# Logic_Engine_-_Rear_SK6812.net
KiCad netlist of a schematic drawn in EAGLE
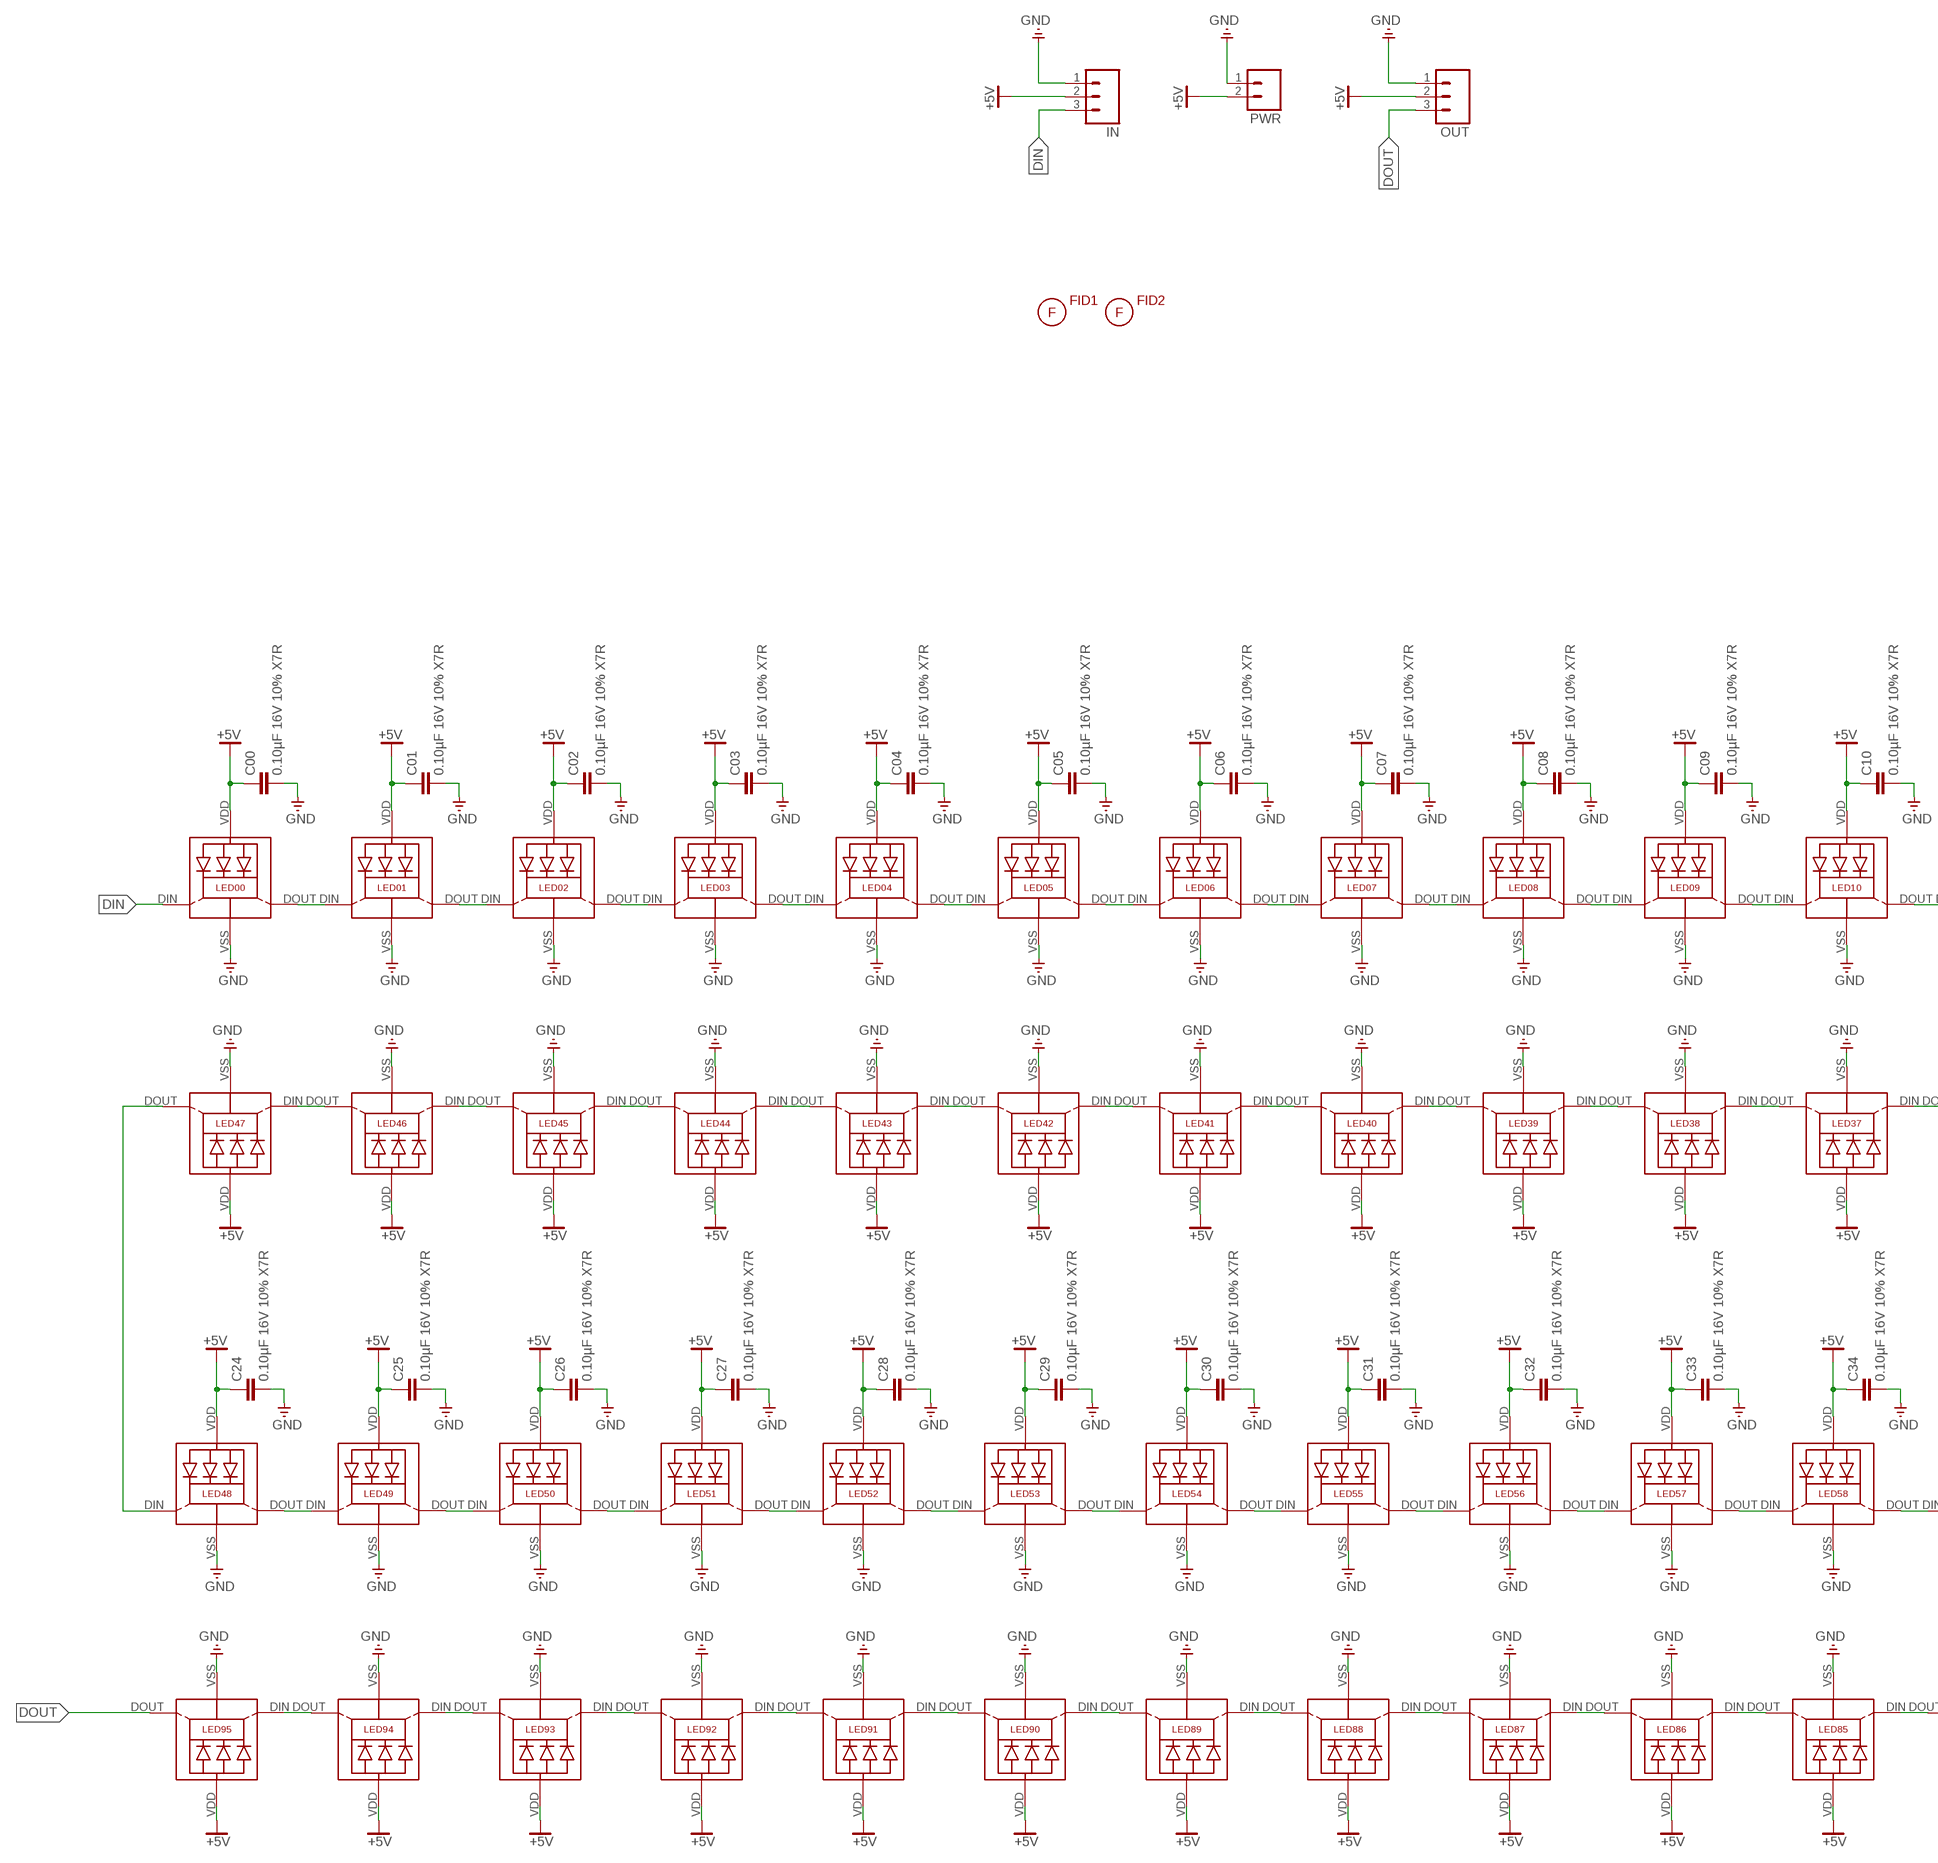
[diagram p0: schematic, sheet 1, part 1 of 2]
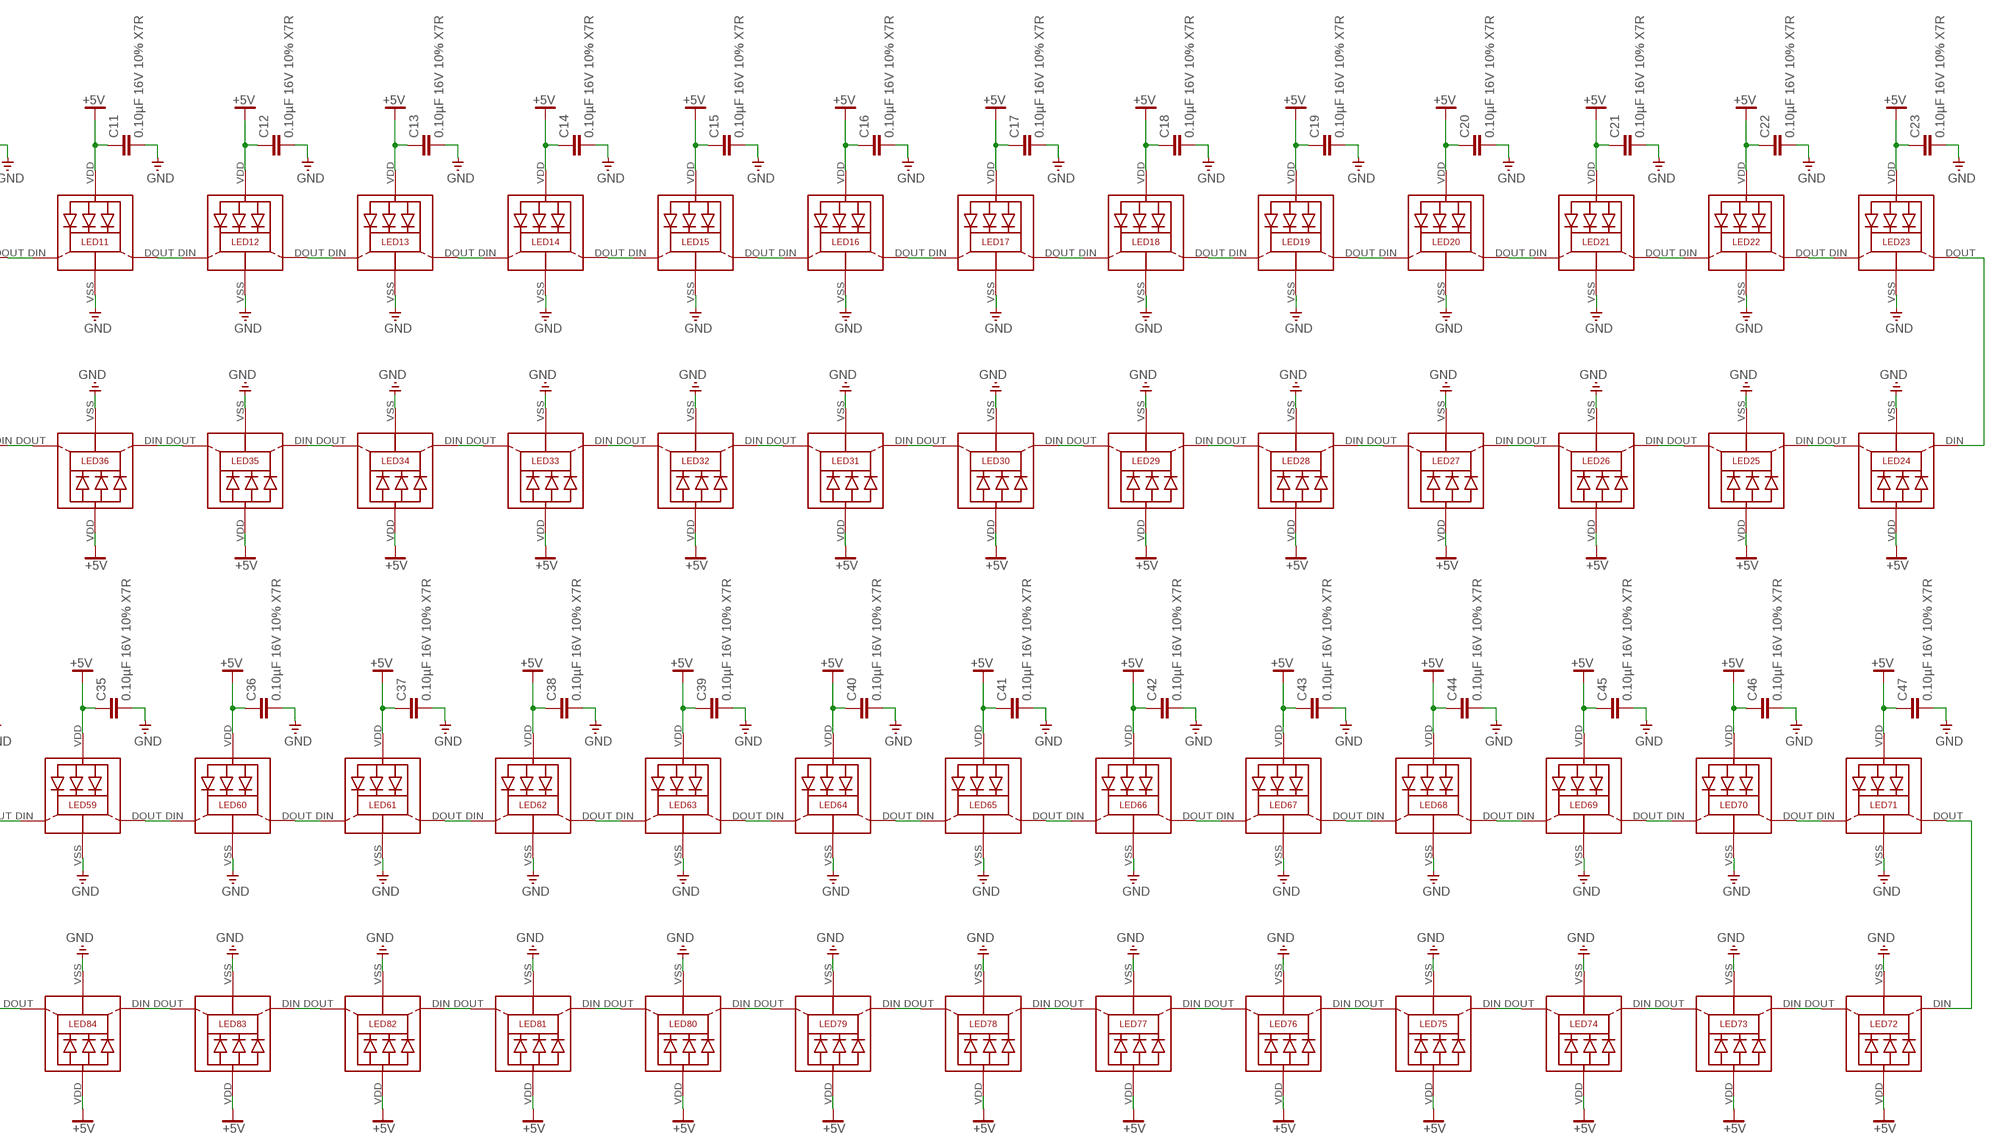
[diagram p1: schematic, sheet 1, part 2 of 2]

(export (version "E")
  (design (tool "Eeschema 10.0.6"))
  (components
    (comp (ref "C00")
      (value "0.10µF 16V 10% X7R")
      (footprint "eagle-import:C0603")
      (libsource (lib "eagle-import") (part "C-EUC0603"))
    )
    (comp (ref "C01")
      (value "0.10µF 16V 10% X7R")
      (footprint "eagle-import:C0603")
      (libsource (lib "eagle-import") (part "C-EUC0603"))
    )
    (comp (ref "C02")
      (value "0.10µF 16V 10% X7R")
      (footprint "eagle-import:C0603")
      (libsource (lib "eagle-import") (part "C-EUC0603"))
    )
    (comp (ref "C03")
      (value "0.10µF 16V 10% X7R")
      (footprint "eagle-import:C0603")
      (libsource (lib "eagle-import") (part "C-EUC0603"))
    )
    (comp (ref "C04")
      (value "0.10µF 16V 10% X7R")
      (footprint "eagle-import:C0603")
      (libsource (lib "eagle-import") (part "C-EUC0603"))
    )
    (comp (ref "C05")
      (value "0.10µF 16V 10% X7R")
      (footprint "eagle-import:C0603")
      (libsource (lib "eagle-import") (part "C-EUC0603"))
    )
    (comp (ref "C06")
      (value "0.10µF 16V 10% X7R")
      (footprint "eagle-import:C0603")
      (libsource (lib "eagle-import") (part "C-EUC0603"))
    )
    (comp (ref "C07")
      (value "0.10µF 16V 10% X7R")
      (footprint "eagle-import:C0603")
      (libsource (lib "eagle-import") (part "C-EUC0603"))
    )
    (comp (ref "C08")
      (value "0.10µF 16V 10% X7R")
      (footprint "eagle-import:C0603")
      (libsource (lib "eagle-import") (part "C-EUC0603"))
    )
    (comp (ref "C09")
      (value "0.10µF 16V 10% X7R")
      (footprint "eagle-import:C0603")
      (libsource (lib "eagle-import") (part "C-EUC0603"))
    )
    (comp (ref "C10")
      (value "0.10µF 16V 10% X7R")
      (footprint "eagle-import:C0603")
      (libsource (lib "eagle-import") (part "C-EUC0603"))
    )
    (comp (ref "C11")
      (value "0.10µF 16V 10% X7R")
      (footprint "eagle-import:C0603")
      (libsource (lib "eagle-import") (part "C-EUC0603"))
    )
    (comp (ref "C12")
      (value "0.10µF 16V 10% X7R")
      (footprint "eagle-import:C0603")
      (libsource (lib "eagle-import") (part "C-EUC0603"))
    )
    (comp (ref "C13")
      (value "0.10µF 16V 10% X7R")
      (footprint "eagle-import:C0603")
      (libsource (lib "eagle-import") (part "C-EUC0603"))
    )
    (comp (ref "C14")
      (value "0.10µF 16V 10% X7R")
      (footprint "eagle-import:C0603")
      (libsource (lib "eagle-import") (part "C-EUC0603"))
    )
    (comp (ref "C15")
      (value "0.10µF 16V 10% X7R")
      (footprint "eagle-import:C0603")
      (libsource (lib "eagle-import") (part "C-EUC0603"))
    )
    (comp (ref "C16")
      (value "0.10µF 16V 10% X7R")
      (footprint "eagle-import:C0603")
      (libsource (lib "eagle-import") (part "C-EUC0603"))
    )
    (comp (ref "C17")
      (value "0.10µF 16V 10% X7R")
      (footprint "eagle-import:C0603")
      (libsource (lib "eagle-import") (part "C-EUC0603"))
    )
    (comp (ref "C18")
      (value "0.10µF 16V 10% X7R")
      (footprint "eagle-import:C0603")
      (libsource (lib "eagle-import") (part "C-EUC0603"))
    )
    (comp (ref "C19")
      (value "0.10µF 16V 10% X7R")
      (footprint "eagle-import:C0603")
      (libsource (lib "eagle-import") (part "C-EUC0603"))
    )
    (comp (ref "C20")
      (value "0.10µF 16V 10% X7R")
      (footprint "eagle-import:C0603")
      (libsource (lib "eagle-import") (part "C-EUC0603"))
    )
    (comp (ref "C21")
      (value "0.10µF 16V 10% X7R")
      (footprint "eagle-import:C0603")
      (libsource (lib "eagle-import") (part "C-EUC0603"))
    )
    (comp (ref "C22")
      (value "0.10µF 16V 10% X7R")
      (footprint "eagle-import:C0603")
      (libsource (lib "eagle-import") (part "C-EUC0603"))
    )
    (comp (ref "C23")
      (value "0.10µF 16V 10% X7R")
      (footprint "eagle-import:C0603")
      (libsource (lib "eagle-import") (part "C-EUC0603"))
    )
    (comp (ref "C24")
      (value "0.10µF 16V 10% X7R")
      (footprint "eagle-import:C0603")
      (libsource (lib "eagle-import") (part "C-EUC0603"))
    )
    (comp (ref "C25")
      (value "0.10µF 16V 10% X7R")
      (footprint "eagle-import:C0603")
      (libsource (lib "eagle-import") (part "C-EUC0603"))
    )
    (comp (ref "C26")
      (value "0.10µF 16V 10% X7R")
      (footprint "eagle-import:C0603")
      (libsource (lib "eagle-import") (part "C-EUC0603"))
    )
    (comp (ref "C27")
      (value "0.10µF 16V 10% X7R")
      (footprint "eagle-import:C0603")
      (libsource (lib "eagle-import") (part "C-EUC0603"))
    )
    (comp (ref "C28")
      (value "0.10µF 16V 10% X7R")
      (footprint "eagle-import:C0603")
      (libsource (lib "eagle-import") (part "C-EUC0603"))
    )
    (comp (ref "C29")
      (value "0.10µF 16V 10% X7R")
      (footprint "eagle-import:C0603")
      (libsource (lib "eagle-import") (part "C-EUC0603"))
    )
    (comp (ref "C30")
      (value "0.10µF 16V 10% X7R")
      (footprint "eagle-import:C0603")
      (libsource (lib "eagle-import") (part "C-EUC0603"))
    )
    (comp (ref "C31")
      (value "0.10µF 16V 10% X7R")
      (footprint "eagle-import:C0603")
      (libsource (lib "eagle-import") (part "C-EUC0603"))
    )
    (comp (ref "C32")
      (value "0.10µF 16V 10% X7R")
      (footprint "eagle-import:C0603")
      (libsource (lib "eagle-import") (part "C-EUC0603"))
    )
    (comp (ref "C33")
      (value "0.10µF 16V 10% X7R")
      (footprint "eagle-import:C0603")
      (libsource (lib "eagle-import") (part "C-EUC0603"))
    )
    (comp (ref "C34")
      (value "0.10µF 16V 10% X7R")
      (footprint "eagle-import:C0603")
      (libsource (lib "eagle-import") (part "C-EUC0603"))
    )
    (comp (ref "C35")
      (value "0.10µF 16V 10% X7R")
      (footprint "eagle-import:C0603")
      (libsource (lib "eagle-import") (part "C-EUC0603"))
    )
    (comp (ref "C36")
      (value "0.10µF 16V 10% X7R")
      (footprint "eagle-import:C0603")
      (libsource (lib "eagle-import") (part "C-EUC0603"))
    )
    (comp (ref "C37")
      (value "0.10µF 16V 10% X7R")
      (footprint "eagle-import:C0603")
      (libsource (lib "eagle-import") (part "C-EUC0603"))
    )
    (comp (ref "C38")
      (value "0.10µF 16V 10% X7R")
      (footprint "eagle-import:C0603")
      (libsource (lib "eagle-import") (part "C-EUC0603"))
    )
    (comp (ref "C39")
      (value "0.10µF 16V 10% X7R")
      (footprint "eagle-import:C0603")
      (libsource (lib "eagle-import") (part "C-EUC0603"))
    )
    (comp (ref "C40")
      (value "0.10µF 16V 10% X7R")
      (footprint "eagle-import:C0603")
      (libsource (lib "eagle-import") (part "C-EUC0603"))
    )
    (comp (ref "C41")
      (value "0.10µF 16V 10% X7R")
      (footprint "eagle-import:C0603")
      (libsource (lib "eagle-import") (part "C-EUC0603"))
    )
    (comp (ref "C42")
      (value "0.10µF 16V 10% X7R")
      (footprint "eagle-import:C0603")
      (libsource (lib "eagle-import") (part "C-EUC0603"))
    )
    (comp (ref "C43")
      (value "0.10µF 16V 10% X7R")
      (footprint "eagle-import:C0603")
      (libsource (lib "eagle-import") (part "C-EUC0603"))
    )
    (comp (ref "C44")
      (value "0.10µF 16V 10% X7R")
      (footprint "eagle-import:C0603")
      (libsource (lib "eagle-import") (part "C-EUC0603"))
    )
    (comp (ref "C45")
      (value "0.10µF 16V 10% X7R")
      (footprint "eagle-import:C0603")
      (libsource (lib "eagle-import") (part "C-EUC0603"))
    )
    (comp (ref "C46")
      (value "0.10µF 16V 10% X7R")
      (footprint "eagle-import:C0603")
      (libsource (lib "eagle-import") (part "C-EUC0603"))
    )
    (comp (ref "C47")
      (value "0.10µF 16V 10% X7R")
      (footprint "eagle-import:C0603")
      (libsource (lib "eagle-import") (part "C-EUC0603"))
    )
    (comp (ref "FID1")
      (value "FIDUCIAL")
      (footprint "eagle-import:FIDUCIAL_G15")
      (libsource (lib "eagle-import") (part "FIDUCIAL"))
    )
    (comp (ref "FID2")
      (value "FIDUCIAL")
      (footprint "eagle-import:FIDUCIAL_G15")
      (libsource (lib "eagle-import") (part "FIDUCIAL"))
    )
    (comp (ref "IN")
      (value "M03PTH")
      (footprint "eagle-import:1X03")
      (libsource (lib "eagle-import") (part "M03PTH"))
    )
    (comp (ref "LED00")
      (value "SK6812MINI")
      (footprint "eagle-import:SK6812MINI")
      (libsource (lib "eagle-import") (part "WS2812BSK6812MINI"))
    )
    (comp (ref "LED01")
      (value "SK6812MINI")
      (footprint "eagle-import:SK6812MINI")
      (libsource (lib "eagle-import") (part "WS2812BSK6812MINI"))
    )
    (comp (ref "LED02")
      (value "SK6812MINI")
      (footprint "eagle-import:SK6812MINI")
      (libsource (lib "eagle-import") (part "WS2812BSK6812MINI"))
    )
    (comp (ref "LED03")
      (value "SK6812MINI")
      (footprint "eagle-import:SK6812MINI")
      (libsource (lib "eagle-import") (part "WS2812BSK6812MINI"))
    )
    (comp (ref "LED04")
      (value "SK6812MINI")
      (footprint "eagle-import:SK6812MINI")
      (libsource (lib "eagle-import") (part "WS2812BSK6812MINI"))
    )
    (comp (ref "LED05")
      (value "SK6812MINI")
      (footprint "eagle-import:SK6812MINI")
      (libsource (lib "eagle-import") (part "WS2812BSK6812MINI"))
    )
    (comp (ref "LED06")
      (value "SK6812MINI")
      (footprint "eagle-import:SK6812MINI")
      (libsource (lib "eagle-import") (part "WS2812BSK6812MINI"))
    )
    (comp (ref "LED07")
      (value "SK6812MINI")
      (footprint "eagle-import:SK6812MINI")
      (libsource (lib "eagle-import") (part "WS2812BSK6812MINI"))
    )
    (comp (ref "LED08")
      (value "SK6812MINI")
      (footprint "eagle-import:SK6812MINI")
      (libsource (lib "eagle-import") (part "WS2812BSK6812MINI"))
    )
    (comp (ref "LED09")
      (value "SK6812MINI")
      (footprint "eagle-import:SK6812MINI")
      (libsource (lib "eagle-import") (part "WS2812BSK6812MINI"))
    )
    (comp (ref "LED10")
      (value "SK6812MINI")
      (footprint "eagle-import:SK6812MINI")
      (libsource (lib "eagle-import") (part "WS2812BSK6812MINI"))
    )
    (comp (ref "LED11")
      (value "SK6812MINI")
      (footprint "eagle-import:SK6812MINI")
      (libsource (lib "eagle-import") (part "WS2812BSK6812MINI"))
    )
    (comp (ref "LED12")
      (value "SK6812MINI")
      (footprint "eagle-import:SK6812MINI")
      (libsource (lib "eagle-import") (part "WS2812BSK6812MINI"))
    )
    (comp (ref "LED13")
      (value "SK6812MINI")
      (footprint "eagle-import:SK6812MINI")
      (libsource (lib "eagle-import") (part "WS2812BSK6812MINI"))
    )
    (comp (ref "LED14")
      (value "SK6812MINI")
      (footprint "eagle-import:SK6812MINI")
      (libsource (lib "eagle-import") (part "WS2812BSK6812MINI"))
    )
    (comp (ref "LED15")
      (value "SK6812MINI")
      (footprint "eagle-import:SK6812MINI")
      (libsource (lib "eagle-import") (part "WS2812BSK6812MINI"))
    )
    (comp (ref "LED16")
      (value "SK6812MINI")
      (footprint "eagle-import:SK6812MINI")
      (libsource (lib "eagle-import") (part "WS2812BSK6812MINI"))
    )
    (comp (ref "LED17")
      (value "SK6812MINI")
      (footprint "eagle-import:SK6812MINI")
      (libsource (lib "eagle-import") (part "WS2812BSK6812MINI"))
    )
    (comp (ref "LED18")
      (value "SK6812MINI")
      (footprint "eagle-import:SK6812MINI")
      (libsource (lib "eagle-import") (part "WS2812BSK6812MINI"))
    )
    (comp (ref "LED19")
      (value "SK6812MINI")
      (footprint "eagle-import:SK6812MINI")
      (libsource (lib "eagle-import") (part "WS2812BSK6812MINI"))
    )
    (comp (ref "LED20")
      (value "SK6812MINI")
      (footprint "eagle-import:SK6812MINI")
      (libsource (lib "eagle-import") (part "WS2812BSK6812MINI"))
    )
    (comp (ref "LED21")
      (value "SK6812MINI")
      (footprint "eagle-import:SK6812MINI")
      (libsource (lib "eagle-import") (part "WS2812BSK6812MINI"))
    )
    (comp (ref "LED22")
      (value "SK6812MINI")
      (footprint "eagle-import:SK6812MINI")
      (libsource (lib "eagle-import") (part "WS2812BSK6812MINI"))
    )
    (comp (ref "LED23")
      (value "SK6812MINI")
      (footprint "eagle-import:SK6812MINI")
      (libsource (lib "eagle-import") (part "WS2812BSK6812MINI"))
    )
    (comp (ref "LED24")
      (value "SK6812MINI")
      (footprint "eagle-import:SK6812MINI")
      (libsource (lib "eagle-import") (part "WS2812BSK6812MINI"))
    )
    (comp (ref "LED25")
      (value "SK6812MINI")
      (footprint "eagle-import:SK6812MINI")
      (libsource (lib "eagle-import") (part "WS2812BSK6812MINI"))
    )
    (comp (ref "LED26")
      (value "SK6812MINI")
      (footprint "eagle-import:SK6812MINI")
      (libsource (lib "eagle-import") (part "WS2812BSK6812MINI"))
    )
    (comp (ref "LED27")
      (value "SK6812MINI")
      (footprint "eagle-import:SK6812MINI")
      (libsource (lib "eagle-import") (part "WS2812BSK6812MINI"))
    )
    (comp (ref "LED28")
      (value "SK6812MINI")
      (footprint "eagle-import:SK6812MINI")
      (libsource (lib "eagle-import") (part "WS2812BSK6812MINI"))
    )
    (comp (ref "LED29")
      (value "SK6812MINI")
      (footprint "eagle-import:SK6812MINI")
      (libsource (lib "eagle-import") (part "WS2812BSK6812MINI"))
    )
    (comp (ref "LED30")
      (value "SK6812MINI")
      (footprint "eagle-import:SK6812MINI")
      (libsource (lib "eagle-import") (part "WS2812BSK6812MINI"))
    )
    (comp (ref "LED31")
      (value "SK6812MINI")
      (footprint "eagle-import:SK6812MINI")
      (libsource (lib "eagle-import") (part "WS2812BSK6812MINI"))
    )
    (comp (ref "LED32")
      (value "SK6812MINI")
      (footprint "eagle-import:SK6812MINI")
      (libsource (lib "eagle-import") (part "WS2812BSK6812MINI"))
    )
    (comp (ref "LED33")
      (value "SK6812MINI")
      (footprint "eagle-import:SK6812MINI")
      (libsource (lib "eagle-import") (part "WS2812BSK6812MINI"))
    )
    (comp (ref "LED34")
      (value "SK6812MINI")
      (footprint "eagle-import:SK6812MINI")
      (libsource (lib "eagle-import") (part "WS2812BSK6812MINI"))
    )
    (comp (ref "LED35")
      (value "SK6812MINI")
      (footprint "eagle-import:SK6812MINI")
      (libsource (lib "eagle-import") (part "WS2812BSK6812MINI"))
    )
    (comp (ref "LED36")
      (value "SK6812MINI")
      (footprint "eagle-import:SK6812MINI")
      (libsource (lib "eagle-import") (part "WS2812BSK6812MINI"))
    )
    (comp (ref "LED37")
      (value "SK6812MINI")
      (footprint "eagle-import:SK6812MINI")
      (libsource (lib "eagle-import") (part "WS2812BSK6812MINI"))
    )
    (comp (ref "LED38")
      (value "SK6812MINI")
      (footprint "eagle-import:SK6812MINI")
      (libsource (lib "eagle-import") (part "WS2812BSK6812MINI"))
    )
    (comp (ref "LED39")
      (value "SK6812MINI")
      (footprint "eagle-import:SK6812MINI")
      (libsource (lib "eagle-import") (part "WS2812BSK6812MINI"))
    )
    (comp (ref "LED40")
      (value "SK6812MINI")
      (footprint "eagle-import:SK6812MINI")
      (libsource (lib "eagle-import") (part "WS2812BSK6812MINI"))
    )
    (comp (ref "LED41")
      (value "SK6812MINI")
      (footprint "eagle-import:SK6812MINI")
      (libsource (lib "eagle-import") (part "WS2812BSK6812MINI"))
    )
    (comp (ref "LED42")
      (value "SK6812MINI")
      (footprint "eagle-import:SK6812MINI")
      (libsource (lib "eagle-import") (part "WS2812BSK6812MINI"))
    )
    (comp (ref "LED43")
      (value "SK6812MINI")
      (footprint "eagle-import:SK6812MINI")
      (libsource (lib "eagle-import") (part "WS2812BSK6812MINI"))
    )
    (comp (ref "LED44")
      (value "SK6812MINI")
      (footprint "eagle-import:SK6812MINI")
      (libsource (lib "eagle-import") (part "WS2812BSK6812MINI"))
    )
    (comp (ref "LED45")
      (value "SK6812MINI")
      (footprint "eagle-import:SK6812MINI")
      (libsource (lib "eagle-import") (part "WS2812BSK6812MINI"))
    )
    (comp (ref "LED46")
      (value "SK6812MINI")
      (footprint "eagle-import:SK6812MINI")
      (libsource (lib "eagle-import") (part "WS2812BSK6812MINI"))
    )
    (comp (ref "LED47")
      (value "SK6812MINI")
      (footprint "eagle-import:SK6812MINI")
      (libsource (lib "eagle-import") (part "WS2812BSK6812MINI"))
    )
    (comp (ref "LED48")
      (value "SK6812MINI")
      (footprint "eagle-import:SK6812MINI")
      (libsource (lib "eagle-import") (part "WS2812BSK6812MINI"))
    )
    (comp (ref "LED49")
      (value "SK6812MINI")
      (footprint "eagle-import:SK6812MINI")
      (libsource (lib "eagle-import") (part "WS2812BSK6812MINI"))
    )
    (comp (ref "LED50")
      (value "SK6812MINI")
      (footprint "eagle-import:SK6812MINI")
      (libsource (lib "eagle-import") (part "WS2812BSK6812MINI"))
    )
    (comp (ref "LED51")
      (value "SK6812MINI")
      (footprint "eagle-import:SK6812MINI")
      (libsource (lib "eagle-import") (part "WS2812BSK6812MINI"))
    )
    (comp (ref "LED52")
      (value "SK6812MINI")
      (footprint "eagle-import:SK6812MINI")
      (libsource (lib "eagle-import") (part "WS2812BSK6812MINI"))
    )
    (comp (ref "LED53")
      (value "SK6812MINI")
      (footprint "eagle-import:SK6812MINI")
      (libsource (lib "eagle-import") (part "WS2812BSK6812MINI"))
    )
    (comp (ref "LED54")
      (value "SK6812MINI")
      (footprint "eagle-import:SK6812MINI")
      (libsource (lib "eagle-import") (part "WS2812BSK6812MINI"))
    )
    (comp (ref "LED55")
      (value "SK6812MINI")
      (footprint "eagle-import:SK6812MINI")
      (libsource (lib "eagle-import") (part "WS2812BSK6812MINI"))
    )
    (comp (ref "LED56")
      (value "SK6812MINI")
      (footprint "eagle-import:SK6812MINI")
      (libsource (lib "eagle-import") (part "WS2812BSK6812MINI"))
    )
    (comp (ref "LED57")
      (value "SK6812MINI")
      (footprint "eagle-import:SK6812MINI")
      (libsource (lib "eagle-import") (part "WS2812BSK6812MINI"))
    )
    (comp (ref "LED58")
      (value "SK6812MINI")
      (footprint "eagle-import:SK6812MINI")
      (libsource (lib "eagle-import") (part "WS2812BSK6812MINI"))
    )
    (comp (ref "LED59")
      (value "SK6812MINI")
      (footprint "eagle-import:SK6812MINI")
      (libsource (lib "eagle-import") (part "WS2812BSK6812MINI"))
    )
    (comp (ref "LED60")
      (value "SK6812MINI")
      (footprint "eagle-import:SK6812MINI")
      (libsource (lib "eagle-import") (part "WS2812BSK6812MINI"))
    )
    (comp (ref "LED61")
      (value "SK6812MINI")
      (footprint "eagle-import:SK6812MINI")
      (libsource (lib "eagle-import") (part "WS2812BSK6812MINI"))
    )
    (comp (ref "LED62")
      (value "SK6812MINI")
      (footprint "eagle-import:SK6812MINI")
      (libsource (lib "eagle-import") (part "WS2812BSK6812MINI"))
    )
    (comp (ref "LED63")
      (value "SK6812MINI")
      (footprint "eagle-import:SK6812MINI")
      (libsource (lib "eagle-import") (part "WS2812BSK6812MINI"))
    )
    (comp (ref "LED64")
      (value "SK6812MINI")
      (footprint "eagle-import:SK6812MINI")
      (libsource (lib "eagle-import") (part "WS2812BSK6812MINI"))
    )
    (comp (ref "LED65")
      (value "SK6812MINI")
      (footprint "eagle-import:SK6812MINI")
      (libsource (lib "eagle-import") (part "WS2812BSK6812MINI"))
    )
    (comp (ref "LED66")
      (value "SK6812MINI")
      (footprint "eagle-import:SK6812MINI")
      (libsource (lib "eagle-import") (part "WS2812BSK6812MINI"))
    )
    (comp (ref "LED67")
      (value "SK6812MINI")
      (footprint "eagle-import:SK6812MINI")
      (libsource (lib "eagle-import") (part "WS2812BSK6812MINI"))
    )
    (comp (ref "LED68")
      (value "SK6812MINI")
      (footprint "eagle-import:SK6812MINI")
      (libsource (lib "eagle-import") (part "WS2812BSK6812MINI"))
    )
    (comp (ref "LED69")
      (value "SK6812MINI")
      (footprint "eagle-import:SK6812MINI")
      (libsource (lib "eagle-import") (part "WS2812BSK6812MINI"))
    )
    (comp (ref "LED70")
      (value "SK6812MINI")
      (footprint "eagle-import:SK6812MINI")
      (libsource (lib "eagle-import") (part "WS2812BSK6812MINI"))
    )
    (comp (ref "LED71")
      (value "SK6812MINI")
      (footprint "eagle-import:SK6812MINI")
      (libsource (lib "eagle-import") (part "WS2812BSK6812MINI"))
    )
    (comp (ref "LED72")
      (value "SK6812MINI")
      (footprint "eagle-import:SK6812MINI")
      (libsource (lib "eagle-import") (part "WS2812BSK6812MINI"))
    )
    (comp (ref "LED73")
      (value "SK6812MINI")
      (footprint "eagle-import:SK6812MINI")
      (libsource (lib "eagle-import") (part "WS2812BSK6812MINI"))
    )
    (comp (ref "LED74")
      (value "SK6812MINI")
      (footprint "eagle-import:SK6812MINI")
      (libsource (lib "eagle-import") (part "WS2812BSK6812MINI"))
    )
    (comp (ref "LED75")
      (value "SK6812MINI")
      (footprint "eagle-import:SK6812MINI")
      (libsource (lib "eagle-import") (part "WS2812BSK6812MINI"))
    )
    (comp (ref "LED76")
      (value "SK6812MINI")
      (footprint "eagle-import:SK6812MINI")
      (libsource (lib "eagle-import") (part "WS2812BSK6812MINI"))
    )
    (comp (ref "LED77")
      (value "SK6812MINI")
      (footprint "eagle-import:SK6812MINI")
      (libsource (lib "eagle-import") (part "WS2812BSK6812MINI"))
    )
    (comp (ref "LED78")
      (value "SK6812MINI")
      (footprint "eagle-import:SK6812MINI")
      (libsource (lib "eagle-import") (part "WS2812BSK6812MINI"))
    )
    (comp (ref "LED79")
      (value "SK6812MINI")
      (footprint "eagle-import:SK6812MINI")
      (libsource (lib "eagle-import") (part "WS2812BSK6812MINI"))
    )
    (comp (ref "LED80")
      (value "SK6812MINI")
      (footprint "eagle-import:SK6812MINI")
      (libsource (lib "eagle-import") (part "WS2812BSK6812MINI"))
    )
    (comp (ref "LED81")
      (value "SK6812MINI")
      (footprint "eagle-import:SK6812MINI")
      (libsource (lib "eagle-import") (part "WS2812BSK6812MINI"))
    )
    (comp (ref "LED82")
      (value "SK6812MINI")
      (footprint "eagle-import:SK6812MINI")
      (libsource (lib "eagle-import") (part "WS2812BSK6812MINI"))
    )
    (comp (ref "LED83")
      (value "SK6812MINI")
      (footprint "eagle-import:SK6812MINI")
      (libsource (lib "eagle-import") (part "WS2812BSK6812MINI"))
    )
    (comp (ref "LED84")
      (value "SK6812MINI")
      (footprint "eagle-import:SK6812MINI")
      (libsource (lib "eagle-import") (part "WS2812BSK6812MINI"))
    )
    (comp (ref "LED85")
      (value "SK6812MINI")
      (footprint "eagle-import:SK6812MINI")
      (libsource (lib "eagle-import") (part "WS2812BSK6812MINI"))
    )
    (comp (ref "LED86")
      (value "SK6812MINI")
      (footprint "eagle-import:SK6812MINI")
      (libsource (lib "eagle-import") (part "WS2812BSK6812MINI"))
    )
    (comp (ref "LED87")
      (value "SK6812MINI")
      (footprint "eagle-import:SK6812MINI")
      (libsource (lib "eagle-import") (part "WS2812BSK6812MINI"))
    )
    (comp (ref "LED88")
      (value "SK6812MINI")
      (footprint "eagle-import:SK6812MINI")
      (libsource (lib "eagle-import") (part "WS2812BSK6812MINI"))
    )
    (comp (ref "LED89")
      (value "SK6812MINI")
      (footprint "eagle-import:SK6812MINI")
      (libsource (lib "eagle-import") (part "WS2812BSK6812MINI"))
    )
    (comp (ref "LED90")
      (value "SK6812MINI")
      (footprint "eagle-import:SK6812MINI")
      (libsource (lib "eagle-import") (part "WS2812BSK6812MINI"))
    )
    (comp (ref "LED91")
      (value "SK6812MINI")
      (footprint "eagle-import:SK6812MINI")
      (libsource (lib "eagle-import") (part "WS2812BSK6812MINI"))
    )
    (comp (ref "LED92")
      (value "SK6812MINI")
      (footprint "eagle-import:SK6812MINI")
      (libsource (lib "eagle-import") (part "WS2812BSK6812MINI"))
    )
    (comp (ref "LED93")
      (value "SK6812MINI")
      (footprint "eagle-import:SK6812MINI")
      (libsource (lib "eagle-import") (part "WS2812BSK6812MINI"))
    )
    (comp (ref "LED94")
      (value "SK6812MINI")
      (footprint "eagle-import:SK6812MINI")
      (libsource (lib "eagle-import") (part "WS2812BSK6812MINI"))
    )
    (comp (ref "LED95")
      (value "SK6812MINI")
      (footprint "eagle-import:SK6812MINI")
      (libsource (lib "eagle-import") (part "WS2812BSK6812MINI"))
    )
    (comp (ref "OUT")
      (value "M03PTH")
      (footprint "eagle-import:1X03")
      (libsource (lib "eagle-import") (part "M03PTH"))
    )
    (comp (ref "PWR")
      (value "M02PTH")
      (footprint "eagle-import:1X02")
      (libsource (lib "eagle-import") (part "M02PTH"))
    )
  )
  (nets
    (net (code "1") (name "+5V") (class "Default")
      (node (ref "C00") (pin "1") (pinfunction "1_1") (pintype "passive"))
      (node (ref "C01") (pin "1") (pinfunction "1_1") (pintype "passive"))
      (node (ref "C02") (pin "1") (pinfunction "1_1") (pintype "passive"))
      (node (ref "C03") (pin "1") (pinfunction "1_1") (pintype "passive"))
      (node (ref "C04") (pin "1") (pinfunction "1_1") (pintype "passive"))
      (node (ref "C05") (pin "1") (pinfunction "1_1") (pintype "passive"))
      (node (ref "C06") (pin "1") (pinfunction "1_1") (pintype "passive"))
      (node (ref "C07") (pin "1") (pinfunction "1_1") (pintype "passive"))
      (node (ref "C08") (pin "1") (pinfunction "1_1") (pintype "passive"))
      (node (ref "C09") (pin "1") (pinfunction "1_1") (pintype "passive"))
      (node (ref "C10") (pin "1") (pinfunction "1_1") (pintype "passive"))
      (node (ref "C11") (pin "1") (pinfunction "1_1") (pintype "passive"))
      (node (ref "C12") (pin "1") (pinfunction "1_1") (pintype "passive"))
      (node (ref "C13") (pin "1") (pinfunction "1_1") (pintype "passive"))
      (node (ref "C14") (pin "1") (pinfunction "1_1") (pintype "passive"))
      (node (ref "C15") (pin "1") (pinfunction "1_1") (pintype "passive"))
      (node (ref "C16") (pin "1") (pinfunction "1_1") (pintype "passive"))
      (node (ref "C17") (pin "1") (pinfunction "1_1") (pintype "passive"))
      (node (ref "C18") (pin "1") (pinfunction "1_1") (pintype "passive"))
      (node (ref "C19") (pin "1") (pinfunction "1_1") (pintype "passive"))
      (node (ref "C20") (pin "1") (pinfunction "1_1") (pintype "passive"))
      (node (ref "C21") (pin "1") (pinfunction "1_1") (pintype "passive"))
      (node (ref "C22") (pin "1") (pinfunction "1_1") (pintype "passive"))
      (node (ref "C23") (pin "1") (pinfunction "1_1") (pintype "passive"))
      (node (ref "C24") (pin "1") (pinfunction "1_1") (pintype "passive"))
      (node (ref "C25") (pin "1") (pinfunction "1_1") (pintype "passive"))
      (node (ref "C26") (pin "1") (pinfunction "1_1") (pintype "passive"))
      (node (ref "C27") (pin "1") (pinfunction "1_1") (pintype "passive"))
      (node (ref "C28") (pin "1") (pinfunction "1_1") (pintype "passive"))
      (node (ref "C29") (pin "1") (pinfunction "1_1") (pintype "passive"))
      (node (ref "C30") (pin "1") (pinfunction "1_1") (pintype "passive"))
      (node (ref "C31") (pin "1") (pinfunction "1_1") (pintype "passive"))
      (node (ref "C32") (pin "1") (pinfunction "1_1") (pintype "passive"))
      (node (ref "C33") (pin "1") (pinfunction "1_1") (pintype "passive"))
      (node (ref "C34") (pin "1") (pinfunction "1_1") (pintype "passive"))
      (node (ref "C35") (pin "1") (pinfunction "1_1") (pintype "passive"))
      (node (ref "C36") (pin "1") (pinfunction "1_1") (pintype "passive"))
      (node (ref "C37") (pin "1") (pinfunction "1_1") (pintype "passive"))
      (node (ref "C38") (pin "1") (pinfunction "1_1") (pintype "passive"))
      (node (ref "C39") (pin "1") (pinfunction "1_1") (pintype "passive"))
      (node (ref "C40") (pin "1") (pinfunction "1_1") (pintype "passive"))
      (node (ref "C41") (pin "1") (pinfunction "1_1") (pintype "passive"))
      (node (ref "C42") (pin "1") (pinfunction "1_1") (pintype "passive"))
      (node (ref "C43") (pin "1") (pinfunction "1_1") (pintype "passive"))
      (node (ref "C44") (pin "1") (pinfunction "1_1") (pintype "passive"))
      (node (ref "C45") (pin "1") (pinfunction "1_1") (pintype "passive"))
      (node (ref "C46") (pin "1") (pinfunction "1_1") (pintype "passive"))
      (node (ref "C47") (pin "1") (pinfunction "1_1") (pintype "passive"))
      (node (ref "IN") (pin "2") (pinfunction "2_2") (pintype "passive"))
      (node (ref "LED00") (pin "VDD") (pinfunction "VDD_VDD") (pintype "power_in"))
      (node (ref "LED01") (pin "VDD") (pinfunction "VDD_VDD") (pintype "power_in"))
      (node (ref "LED02") (pin "VDD") (pinfunction "VDD_VDD") (pintype "power_in"))
      (node (ref "LED03") (pin "VDD") (pinfunction "VDD_VDD") (pintype "power_in"))
      (node (ref "LED04") (pin "VDD") (pinfunction "VDD_VDD") (pintype "power_in"))
      (node (ref "LED05") (pin "VDD") (pinfunction "VDD_VDD") (pintype "power_in"))
      (node (ref "LED06") (pin "VDD") (pinfunction "VDD_VDD") (pintype "power_in"))
      (node (ref "LED07") (pin "VDD") (pinfunction "VDD_VDD") (pintype "power_in"))
      (node (ref "LED08") (pin "VDD") (pinfunction "VDD_VDD") (pintype "power_in"))
      (node (ref "LED09") (pin "VDD") (pinfunction "VDD_VDD") (pintype "power_in"))
      (node (ref "LED10") (pin "VDD") (pinfunction "VDD_VDD") (pintype "power_in"))
      (node (ref "LED11") (pin "VDD") (pinfunction "VDD_VDD") (pintype "power_in"))
      (node (ref "LED12") (pin "VDD") (pinfunction "VDD_VDD") (pintype "power_in"))
      (node (ref "LED13") (pin "VDD") (pinfunction "VDD_VDD") (pintype "power_in"))
      (node (ref "LED14") (pin "VDD") (pinfunction "VDD_VDD") (pintype "power_in"))
      (node (ref "LED15") (pin "VDD") (pinfunction "VDD_VDD") (pintype "power_in"))
      (node (ref "LED16") (pin "VDD") (pinfunction "VDD_VDD") (pintype "power_in"))
      (node (ref "LED17") (pin "VDD") (pinfunction "VDD_VDD") (pintype "power_in"))
      (node (ref "LED18") (pin "VDD") (pinfunction "VDD_VDD") (pintype "power_in"))
      (node (ref "LED19") (pin "VDD") (pinfunction "VDD_VDD") (pintype "power_in"))
      (node (ref "LED20") (pin "VDD") (pinfunction "VDD_VDD") (pintype "power_in"))
      (node (ref "LED21") (pin "VDD") (pinfunction "VDD_VDD") (pintype "power_in"))
      (node (ref "LED22") (pin "VDD") (pinfunction "VDD_VDD") (pintype "power_in"))
      (node (ref "LED23") (pin "VDD") (pinfunction "VDD_VDD") (pintype "power_in"))
      (node (ref "LED24") (pin "VDD") (pinfunction "VDD_VDD") (pintype "power_in"))
      (node (ref "LED25") (pin "VDD") (pinfunction "VDD_VDD") (pintype "power_in"))
      (node (ref "LED26") (pin "VDD") (pinfunction "VDD_VDD") (pintype "power_in"))
      (node (ref "LED27") (pin "VDD") (pinfunction "VDD_VDD") (pintype "power_in"))
      (node (ref "LED28") (pin "VDD") (pinfunction "VDD_VDD") (pintype "power_in"))
      (node (ref "LED29") (pin "VDD") (pinfunction "VDD_VDD") (pintype "power_in"))
      (node (ref "LED30") (pin "VDD") (pinfunction "VDD_VDD") (pintype "power_in"))
      (node (ref "LED31") (pin "VDD") (pinfunction "VDD_VDD") (pintype "power_in"))
      (node (ref "LED32") (pin "VDD") (pinfunction "VDD_VDD") (pintype "power_in"))
      (node (ref "LED33") (pin "VDD") (pinfunction "VDD_VDD") (pintype "power_in"))
      (node (ref "LED34") (pin "VDD") (pinfunction "VDD_VDD") (pintype "power_in"))
      (node (ref "LED35") (pin "VDD") (pinfunction "VDD_VDD") (pintype "power_in"))
      (node (ref "LED36") (pin "VDD") (pinfunction "VDD_VDD") (pintype "power_in"))
      (node (ref "LED37") (pin "VDD") (pinfunction "VDD_VDD") (pintype "power_in"))
      (node (ref "LED38") (pin "VDD") (pinfunction "VDD_VDD") (pintype "power_in"))
      (node (ref "LED39") (pin "VDD") (pinfunction "VDD_VDD") (pintype "power_in"))
      (node (ref "LED40") (pin "VDD") (pinfunction "VDD_VDD") (pintype "power_in"))
      (node (ref "LED41") (pin "VDD") (pinfunction "VDD_VDD") (pintype "power_in"))
      (node (ref "LED42") (pin "VDD") (pinfunction "VDD_VDD") (pintype "power_in"))
      (node (ref "LED43") (pin "VDD") (pinfunction "VDD_VDD") (pintype "power_in"))
      (node (ref "LED44") (pin "VDD") (pinfunction "VDD_VDD") (pintype "power_in"))
      (node (ref "LED45") (pin "VDD") (pinfunction "VDD_VDD") (pintype "power_in"))
      (node (ref "LED46") (pin "VDD") (pinfunction "VDD_VDD") (pintype "power_in"))
      (node (ref "LED47") (pin "VDD") (pinfunction "VDD_VDD") (pintype "power_in"))
      (node (ref "LED48") (pin "VDD") (pinfunction "VDD_VDD") (pintype "power_in"))
      (node (ref "LED49") (pin "VDD") (pinfunction "VDD_VDD") (pintype "power_in"))
      (node (ref "LED50") (pin "VDD") (pinfunction "VDD_VDD") (pintype "power_in"))
      (node (ref "LED51") (pin "VDD") (pinfunction "VDD_VDD") (pintype "power_in"))
      (node (ref "LED52") (pin "VDD") (pinfunction "VDD_VDD") (pintype "power_in"))
      (node (ref "LED53") (pin "VDD") (pinfunction "VDD_VDD") (pintype "power_in"))
      (node (ref "LED54") (pin "VDD") (pinfunction "VDD_VDD") (pintype "power_in"))
      (node (ref "LED55") (pin "VDD") (pinfunction "VDD_VDD") (pintype "power_in"))
      (node (ref "LED56") (pin "VDD") (pinfunction "VDD_VDD") (pintype "power_in"))
      (node (ref "LED57") (pin "VDD") (pinfunction "VDD_VDD") (pintype "power_in"))
      (node (ref "LED58") (pin "VDD") (pinfunction "VDD_VDD") (pintype "power_in"))
      (node (ref "LED59") (pin "VDD") (pinfunction "VDD_VDD") (pintype "power_in"))
      (node (ref "LED60") (pin "VDD") (pinfunction "VDD_VDD") (pintype "power_in"))
      (node (ref "LED61") (pin "VDD") (pinfunction "VDD_VDD") (pintype "power_in"))
      (node (ref "LED62") (pin "VDD") (pinfunction "VDD_VDD") (pintype "power_in"))
      (node (ref "LED63") (pin "VDD") (pinfunction "VDD_VDD") (pintype "power_in"))
      (node (ref "LED64") (pin "VDD") (pinfunction "VDD_VDD") (pintype "power_in"))
      (node (ref "LED65") (pin "VDD") (pinfunction "VDD_VDD") (pintype "power_in"))
      (node (ref "LED66") (pin "VDD") (pinfunction "VDD_VDD") (pintype "power_in"))
      (node (ref "LED67") (pin "VDD") (pinfunction "VDD_VDD") (pintype "power_in"))
      (node (ref "LED68") (pin "VDD") (pinfunction "VDD_VDD") (pintype "power_in"))
      (node (ref "LED69") (pin "VDD") (pinfunction "VDD_VDD") (pintype "power_in"))
      (node (ref "LED70") (pin "VDD") (pinfunction "VDD_VDD") (pintype "power_in"))
      (node (ref "LED71") (pin "VDD") (pinfunction "VDD_VDD") (pintype "power_in"))
      (node (ref "LED72") (pin "VDD") (pinfunction "VDD_VDD") (pintype "power_in"))
      (node (ref "LED73") (pin "VDD") (pinfunction "VDD_VDD") (pintype "power_in"))
      (node (ref "LED74") (pin "VDD") (pinfunction "VDD_VDD") (pintype "power_in"))
      (node (ref "LED75") (pin "VDD") (pinfunction "VDD_VDD") (pintype "power_in"))
      (node (ref "LED76") (pin "VDD") (pinfunction "VDD_VDD") (pintype "power_in"))
      (node (ref "LED77") (pin "VDD") (pinfunction "VDD_VDD") (pintype "power_in"))
      (node (ref "LED78") (pin "VDD") (pinfunction "VDD_VDD") (pintype "power_in"))
      (node (ref "LED79") (pin "VDD") (pinfunction "VDD_VDD") (pintype "power_in"))
      (node (ref "LED80") (pin "VDD") (pinfunction "VDD_VDD") (pintype "power_in"))
      (node (ref "LED81") (pin "VDD") (pinfunction "VDD_VDD") (pintype "power_in"))
      (node (ref "LED82") (pin "VDD") (pinfunction "VDD_VDD") (pintype "power_in"))
      (node (ref "LED83") (pin "VDD") (pinfunction "VDD_VDD") (pintype "power_in"))
      (node (ref "LED84") (pin "VDD") (pinfunction "VDD_VDD") (pintype "power_in"))
      (node (ref "LED85") (pin "VDD") (pinfunction "VDD_VDD") (pintype "power_in"))
      (node (ref "LED86") (pin "VDD") (pinfunction "VDD_VDD") (pintype "power_in"))
      (node (ref "LED87") (pin "VDD") (pinfunction "VDD_VDD") (pintype "power_in"))
      (node (ref "LED88") (pin "VDD") (pinfunction "VDD_VDD") (pintype "power_in"))
      (node (ref "LED89") (pin "VDD") (pinfunction "VDD_VDD") (pintype "power_in"))
      (node (ref "LED90") (pin "VDD") (pinfunction "VDD_VDD") (pintype "power_in"))
      (node (ref "LED91") (pin "VDD") (pinfunction "VDD_VDD") (pintype "power_in"))
      (node (ref "LED92") (pin "VDD") (pinfunction "VDD_VDD") (pintype "power_in"))
      (node (ref "LED93") (pin "VDD") (pinfunction "VDD_VDD") (pintype "power_in"))
      (node (ref "LED94") (pin "VDD") (pinfunction "VDD_VDD") (pintype "power_in"))
      (node (ref "LED95") (pin "VDD") (pinfunction "VDD_VDD") (pintype "power_in"))
      (node (ref "OUT") (pin "2") (pinfunction "2_2") (pintype "passive"))
      (node (ref "PWR") (pin "2") (pinfunction "2_2") (pintype "passive"))
    )
    (net (code "2") (name "DIN") (class "Default")
      (node (ref "IN") (pin "3") (pinfunction "3_3") (pintype "passive"))
      (node (ref "LED00") (pin "DIN") (pinfunction "DI_DIN") (pintype "input"))
    )
    (net (code "3") (name "DOUT") (class "Default")
      (node (ref "LED95") (pin "DOUT") (pinfunction "DO_DOUT") (pintype "output"))
      (node (ref "OUT") (pin "3") (pinfunction "3_3") (pintype "passive"))
    )
    (net (code "4") (name "GND") (class "Default")
      (node (ref "C00") (pin "2") (pinfunction "2_2") (pintype "passive"))
      (node (ref "C01") (pin "2") (pinfunction "2_2") (pintype "passive"))
      (node (ref "C02") (pin "2") (pinfunction "2_2") (pintype "passive"))
      (node (ref "C03") (pin "2") (pinfunction "2_2") (pintype "passive"))
      (node (ref "C04") (pin "2") (pinfunction "2_2") (pintype "passive"))
      (node (ref "C05") (pin "2") (pinfunction "2_2") (pintype "passive"))
      (node (ref "C06") (pin "2") (pinfunction "2_2") (pintype "passive"))
      (node (ref "C07") (pin "2") (pinfunction "2_2") (pintype "passive"))
      (node (ref "C08") (pin "2") (pinfunction "2_2") (pintype "passive"))
      (node (ref "C09") (pin "2") (pinfunction "2_2") (pintype "passive"))
      (node (ref "C10") (pin "2") (pinfunction "2_2") (pintype "passive"))
      (node (ref "C11") (pin "2") (pinfunction "2_2") (pintype "passive"))
      (node (ref "C12") (pin "2") (pinfunction "2_2") (pintype "passive"))
      (node (ref "C13") (pin "2") (pinfunction "2_2") (pintype "passive"))
      (node (ref "C14") (pin "2") (pinfunction "2_2") (pintype "passive"))
      (node (ref "C15") (pin "2") (pinfunction "2_2") (pintype "passive"))
      (node (ref "C16") (pin "2") (pinfunction "2_2") (pintype "passive"))
      (node (ref "C17") (pin "2") (pinfunction "2_2") (pintype "passive"))
      (node (ref "C18") (pin "2") (pinfunction "2_2") (pintype "passive"))
      (node (ref "C19") (pin "2") (pinfunction "2_2") (pintype "passive"))
      (node (ref "C20") (pin "2") (pinfunction "2_2") (pintype "passive"))
      (node (ref "C21") (pin "2") (pinfunction "2_2") (pintype "passive"))
      (node (ref "C22") (pin "2") (pinfunction "2_2") (pintype "passive"))
      (node (ref "C23") (pin "2") (pinfunction "2_2") (pintype "passive"))
      (node (ref "C24") (pin "2") (pinfunction "2_2") (pintype "passive"))
      (node (ref "C25") (pin "2") (pinfunction "2_2") (pintype "passive"))
      (node (ref "C26") (pin "2") (pinfunction "2_2") (pintype "passive"))
      (node (ref "C27") (pin "2") (pinfunction "2_2") (pintype "passive"))
      (node (ref "C28") (pin "2") (pinfunction "2_2") (pintype "passive"))
      (node (ref "C29") (pin "2") (pinfunction "2_2") (pintype "passive"))
      (node (ref "C30") (pin "2") (pinfunction "2_2") (pintype "passive"))
      (node (ref "C31") (pin "2") (pinfunction "2_2") (pintype "passive"))
      (node (ref "C32") (pin "2") (pinfunction "2_2") (pintype "passive"))
      (node (ref "C33") (pin "2") (pinfunction "2_2") (pintype "passive"))
      (node (ref "C34") (pin "2") (pinfunction "2_2") (pintype "passive"))
      (node (ref "C35") (pin "2") (pinfunction "2_2") (pintype "passive"))
      (node (ref "C36") (pin "2") (pinfunction "2_2") (pintype "passive"))
      (node (ref "C37") (pin "2") (pinfunction "2_2") (pintype "passive"))
      (node (ref "C38") (pin "2") (pinfunction "2_2") (pintype "passive"))
      (node (ref "C39") (pin "2") (pinfunction "2_2") (pintype "passive"))
      (node (ref "C40") (pin "2") (pinfunction "2_2") (pintype "passive"))
      (node (ref "C41") (pin "2") (pinfunction "2_2") (pintype "passive"))
      (node (ref "C42") (pin "2") (pinfunction "2_2") (pintype "passive"))
      (node (ref "C43") (pin "2") (pinfunction "2_2") (pintype "passive"))
      (node (ref "C44") (pin "2") (pinfunction "2_2") (pintype "passive"))
      (node (ref "C45") (pin "2") (pinfunction "2_2") (pintype "passive"))
      (node (ref "C46") (pin "2") (pinfunction "2_2") (pintype "passive"))
      (node (ref "C47") (pin "2") (pinfunction "2_2") (pintype "passive"))
      (node (ref "IN") (pin "1") (pinfunction "1_1") (pintype "passive"))
      (node (ref "LED00") (pin "VSS") (pinfunction "GND_VSS") (pintype "power_in"))
      (node (ref "LED01") (pin "VSS") (pinfunction "GND_VSS") (pintype "power_in"))
      (node (ref "LED02") (pin "VSS") (pinfunction "GND_VSS") (pintype "power_in"))
      (node (ref "LED03") (pin "VSS") (pinfunction "GND_VSS") (pintype "power_in"))
      (node (ref "LED04") (pin "VSS") (pinfunction "GND_VSS") (pintype "power_in"))
      (node (ref "LED05") (pin "VSS") (pinfunction "GND_VSS") (pintype "power_in"))
      (node (ref "LED06") (pin "VSS") (pinfunction "GND_VSS") (pintype "power_in"))
      (node (ref "LED07") (pin "VSS") (pinfunction "GND_VSS") (pintype "power_in"))
      (node (ref "LED08") (pin "VSS") (pinfunction "GND_VSS") (pintype "power_in"))
      (node (ref "LED09") (pin "VSS") (pinfunction "GND_VSS") (pintype "power_in"))
      (node (ref "LED10") (pin "VSS") (pinfunction "GND_VSS") (pintype "power_in"))
      (node (ref "LED11") (pin "VSS") (pinfunction "GND_VSS") (pintype "power_in"))
      (node (ref "LED12") (pin "VSS") (pinfunction "GND_VSS") (pintype "power_in"))
      (node (ref "LED13") (pin "VSS") (pinfunction "GND_VSS") (pintype "power_in"))
      (node (ref "LED14") (pin "VSS") (pinfunction "GND_VSS") (pintype "power_in"))
      (node (ref "LED15") (pin "VSS") (pinfunction "GND_VSS") (pintype "power_in"))
      (node (ref "LED16") (pin "VSS") (pinfunction "GND_VSS") (pintype "power_in"))
      (node (ref "LED17") (pin "VSS") (pinfunction "GND_VSS") (pintype "power_in"))
      (node (ref "LED18") (pin "VSS") (pinfunction "GND_VSS") (pintype "power_in"))
      (node (ref "LED19") (pin "VSS") (pinfunction "GND_VSS") (pintype "power_in"))
      (node (ref "LED20") (pin "VSS") (pinfunction "GND_VSS") (pintype "power_in"))
      (node (ref "LED21") (pin "VSS") (pinfunction "GND_VSS") (pintype "power_in"))
      (node (ref "LED22") (pin "VSS") (pinfunction "GND_VSS") (pintype "power_in"))
      (node (ref "LED23") (pin "VSS") (pinfunction "GND_VSS") (pintype "power_in"))
      (node (ref "LED24") (pin "VSS") (pinfunction "GND_VSS") (pintype "power_in"))
      (node (ref "LED25") (pin "VSS") (pinfunction "GND_VSS") (pintype "power_in"))
      (node (ref "LED26") (pin "VSS") (pinfunction "GND_VSS") (pintype "power_in"))
      (node (ref "LED27") (pin "VSS") (pinfunction "GND_VSS") (pintype "power_in"))
      (node (ref "LED28") (pin "VSS") (pinfunction "GND_VSS") (pintype "power_in"))
      (node (ref "LED29") (pin "VSS") (pinfunction "GND_VSS") (pintype "power_in"))
      (node (ref "LED30") (pin "VSS") (pinfunction "GND_VSS") (pintype "power_in"))
      (node (ref "LED31") (pin "VSS") (pinfunction "GND_VSS") (pintype "power_in"))
      (node (ref "LED32") (pin "VSS") (pinfunction "GND_VSS") (pintype "power_in"))
      (node (ref "LED33") (pin "VSS") (pinfunction "GND_VSS") (pintype "power_in"))
      (node (ref "LED34") (pin "VSS") (pinfunction "GND_VSS") (pintype "power_in"))
      (node (ref "LED35") (pin "VSS") (pinfunction "GND_VSS") (pintype "power_in"))
      (node (ref "LED36") (pin "VSS") (pinfunction "GND_VSS") (pintype "power_in"))
      (node (ref "LED37") (pin "VSS") (pinfunction "GND_VSS") (pintype "power_in"))
      (node (ref "LED38") (pin "VSS") (pinfunction "GND_VSS") (pintype "power_in"))
      (node (ref "LED39") (pin "VSS") (pinfunction "GND_VSS") (pintype "power_in"))
      (node (ref "LED40") (pin "VSS") (pinfunction "GND_VSS") (pintype "power_in"))
      (node (ref "LED41") (pin "VSS") (pinfunction "GND_VSS") (pintype "power_in"))
      (node (ref "LED42") (pin "VSS") (pinfunction "GND_VSS") (pintype "power_in"))
      (node (ref "LED43") (pin "VSS") (pinfunction "GND_VSS") (pintype "power_in"))
      (node (ref "LED44") (pin "VSS") (pinfunction "GND_VSS") (pintype "power_in"))
      (node (ref "LED45") (pin "VSS") (pinfunction "GND_VSS") (pintype "power_in"))
      (node (ref "LED46") (pin "VSS") (pinfunction "GND_VSS") (pintype "power_in"))
      (node (ref "LED47") (pin "VSS") (pinfunction "GND_VSS") (pintype "power_in"))
      (node (ref "LED48") (pin "VSS") (pinfunction "GND_VSS") (pintype "power_in"))
      (node (ref "LED49") (pin "VSS") (pinfunction "GND_VSS") (pintype "power_in"))
      (node (ref "LED50") (pin "VSS") (pinfunction "GND_VSS") (pintype "power_in"))
      (node (ref "LED51") (pin "VSS") (pinfunction "GND_VSS") (pintype "power_in"))
      (node (ref "LED52") (pin "VSS") (pinfunction "GND_VSS") (pintype "power_in"))
      (node (ref "LED53") (pin "VSS") (pinfunction "GND_VSS") (pintype "power_in"))
      (node (ref "LED54") (pin "VSS") (pinfunction "GND_VSS") (pintype "power_in"))
      (node (ref "LED55") (pin "VSS") (pinfunction "GND_VSS") (pintype "power_in"))
      (node (ref "LED56") (pin "VSS") (pinfunction "GND_VSS") (pintype "power_in"))
      (node (ref "LED57") (pin "VSS") (pinfunction "GND_VSS") (pintype "power_in"))
      (node (ref "LED58") (pin "VSS") (pinfunction "GND_VSS") (pintype "power_in"))
      (node (ref "LED59") (pin "VSS") (pinfunction "GND_VSS") (pintype "power_in"))
      (node (ref "LED60") (pin "VSS") (pinfunction "GND_VSS") (pintype "power_in"))
      (node (ref "LED61") (pin "VSS") (pinfunction "GND_VSS") (pintype "power_in"))
      (node (ref "LED62") (pin "VSS") (pinfunction "GND_VSS") (pintype "power_in"))
      (node (ref "LED63") (pin "VSS") (pinfunction "GND_VSS") (pintype "power_in"))
      (node (ref "LED64") (pin "VSS") (pinfunction "GND_VSS") (pintype "power_in"))
      (node (ref "LED65") (pin "VSS") (pinfunction "GND_VSS") (pintype "power_in"))
      (node (ref "LED66") (pin "VSS") (pinfunction "GND_VSS") (pintype "power_in"))
      (node (ref "LED67") (pin "VSS") (pinfunction "GND_VSS") (pintype "power_in"))
      (node (ref "LED68") (pin "VSS") (pinfunction "GND_VSS") (pintype "power_in"))
      (node (ref "LED69") (pin "VSS") (pinfunction "GND_VSS") (pintype "power_in"))
      (node (ref "LED70") (pin "VSS") (pinfunction "GND_VSS") (pintype "power_in"))
      (node (ref "LED71") (pin "VSS") (pinfunction "GND_VSS") (pintype "power_in"))
      (node (ref "LED72") (pin "VSS") (pinfunction "GND_VSS") (pintype "power_in"))
      (node (ref "LED73") (pin "VSS") (pinfunction "GND_VSS") (pintype "power_in"))
      (node (ref "LED74") (pin "VSS") (pinfunction "GND_VSS") (pintype "power_in"))
      (node (ref "LED75") (pin "VSS") (pinfunction "GND_VSS") (pintype "power_in"))
      (node (ref "LED76") (pin "VSS") (pinfunction "GND_VSS") (pintype "power_in"))
      (node (ref "LED77") (pin "VSS") (pinfunction "GND_VSS") (pintype "power_in"))
      (node (ref "LED78") (pin "VSS") (pinfunction "GND_VSS") (pintype "power_in"))
      (node (ref "LED79") (pin "VSS") (pinfunction "GND_VSS") (pintype "power_in"))
      (node (ref "LED80") (pin "VSS") (pinfunction "GND_VSS") (pintype "power_in"))
      (node (ref "LED81") (pin "VSS") (pinfunction "GND_VSS") (pintype "power_in"))
      (node (ref "LED82") (pin "VSS") (pinfunction "GND_VSS") (pintype "power_in"))
      (node (ref "LED83") (pin "VSS") (pinfunction "GND_VSS") (pintype "power_in"))
      (node (ref "LED84") (pin "VSS") (pinfunction "GND_VSS") (pintype "power_in"))
      (node (ref "LED85") (pin "VSS") (pinfunction "GND_VSS") (pintype "power_in"))
      (node (ref "LED86") (pin "VSS") (pinfunction "GND_VSS") (pintype "power_in"))
      (node (ref "LED87") (pin "VSS") (pinfunction "GND_VSS") (pintype "power_in"))
      (node (ref "LED88") (pin "VSS") (pinfunction "GND_VSS") (pintype "power_in"))
      (node (ref "LED89") (pin "VSS") (pinfunction "GND_VSS") (pintype "power_in"))
      (node (ref "LED90") (pin "VSS") (pinfunction "GND_VSS") (pintype "power_in"))
      (node (ref "LED91") (pin "VSS") (pinfunction "GND_VSS") (pintype "power_in"))
      (node (ref "LED92") (pin "VSS") (pinfunction "GND_VSS") (pintype "power_in"))
      (node (ref "LED93") (pin "VSS") (pinfunction "GND_VSS") (pintype "power_in"))
      (node (ref "LED94") (pin "VSS") (pinfunction "GND_VSS") (pintype "power_in"))
      (node (ref "LED95") (pin "VSS") (pinfunction "GND_VSS") (pintype "power_in"))
      (node (ref "OUT") (pin "1") (pinfunction "1_1") (pintype "passive"))
      (node (ref "PWR") (pin "1") (pinfunction "1_1") (pintype "passive"))
    )
    (net (code "5") (name "Net-(LED00-DO)") (class "Default")
      (node (ref "LED00") (pin "DOUT") (pinfunction "DO_DOUT") (pintype "output"))
      (node (ref "LED01") (pin "DIN") (pinfunction "DI_DIN") (pintype "input"))
    )
    (net (code "6") (name "Net-(LED01-DO)") (class "Default")
      (node (ref "LED01") (pin "DOUT") (pinfunction "DO_DOUT") (pintype "output"))
      (node (ref "LED02") (pin "DIN") (pinfunction "DI_DIN") (pintype "input"))
    )
    (net (code "7") (name "Net-(LED02-DO)") (class "Default")
      (node (ref "LED02") (pin "DOUT") (pinfunction "DO_DOUT") (pintype "output"))
      (node (ref "LED03") (pin "DIN") (pinfunction "DI_DIN") (pintype "input"))
    )
    (net (code "8") (name "Net-(LED03-DO)") (class "Default")
      (node (ref "LED03") (pin "DOUT") (pinfunction "DO_DOUT") (pintype "output"))
      (node (ref "LED04") (pin "DIN") (pinfunction "DI_DIN") (pintype "input"))
    )
    (net (code "9") (name "Net-(LED04-DO)") (class "Default")
      (node (ref "LED04") (pin "DOUT") (pinfunction "DO_DOUT") (pintype "output"))
      (node (ref "LED05") (pin "DIN") (pinfunction "DI_DIN") (pintype "input"))
    )
    (net (code "10") (name "Net-(LED05-DO)") (class "Default")
      (node (ref "LED05") (pin "DOUT") (pinfunction "DO_DOUT") (pintype "output"))
      (node (ref "LED06") (pin "DIN") (pinfunction "DI_DIN") (pintype "input"))
    )
    (net (code "11") (name "Net-(LED06-DO)") (class "Default")
      (node (ref "LED06") (pin "DOUT") (pinfunction "DO_DOUT") (pintype "output"))
      (node (ref "LED07") (pin "DIN") (pinfunction "DI_DIN") (pintype "input"))
    )
    (net (code "12") (name "Net-(LED07-DO)") (class "Default")
      (node (ref "LED07") (pin "DOUT") (pinfunction "DO_DOUT") (pintype "output"))
      (node (ref "LED08") (pin "DIN") (pinfunction "DI_DIN") (pintype "input"))
    )
    (net (code "13") (name "Net-(LED08-DO)") (class "Default")
      (node (ref "LED08") (pin "DOUT") (pinfunction "DO_DOUT") (pintype "output"))
      (node (ref "LED09") (pin "DIN") (pinfunction "DI_DIN") (pintype "input"))
    )
    (net (code "14") (name "Net-(LED09-DO)") (class "Default")
      (node (ref "LED09") (pin "DOUT") (pinfunction "DO_DOUT") (pintype "output"))
      (node (ref "LED10") (pin "DIN") (pinfunction "DI_DIN") (pintype "input"))
    )
    (net (code "15") (name "Net-(LED10-DO)") (class "Default")
      (node (ref "LED10") (pin "DOUT") (pinfunction "DO_DOUT") (pintype "output"))
      (node (ref "LED11") (pin "DIN") (pinfunction "DI_DIN") (pintype "input"))
    )
    (net (code "16") (name "Net-(LED11-DO)") (class "Default")
      (node (ref "LED11") (pin "DOUT") (pinfunction "DO_DOUT") (pintype "output"))
      (node (ref "LED12") (pin "DIN") (pinfunction "DI_DIN") (pintype "input"))
    )
    (net (code "17") (name "Net-(LED12-DO)") (class "Default")
      (node (ref "LED12") (pin "DOUT") (pinfunction "DO_DOUT") (pintype "output"))
      (node (ref "LED13") (pin "DIN") (pinfunction "DI_DIN") (pintype "input"))
    )
    (net (code "18") (name "Net-(LED13-DO)") (class "Default")
      (node (ref "LED13") (pin "DOUT") (pinfunction "DO_DOUT") (pintype "output"))
      (node (ref "LED14") (pin "DIN") (pinfunction "DI_DIN") (pintype "input"))
    )
    (net (code "19") (name "Net-(LED14-DO)") (class "Default")
      (node (ref "LED14") (pin "DOUT") (pinfunction "DO_DOUT") (pintype "output"))
      (node (ref "LED15") (pin "DIN") (pinfunction "DI_DIN") (pintype "input"))
    )
    (net (code "20") (name "Net-(LED15-DO)") (class "Default")
      (node (ref "LED15") (pin "DOUT") (pinfunction "DO_DOUT") (pintype "output"))
      (node (ref "LED16") (pin "DIN") (pinfunction "DI_DIN") (pintype "input"))
    )
    (net (code "21") (name "Net-(LED16-DO)") (class "Default")
      (node (ref "LED16") (pin "DOUT") (pinfunction "DO_DOUT") (pintype "output"))
      (node (ref "LED17") (pin "DIN") (pinfunction "DI_DIN") (pintype "input"))
    )
    (net (code "22") (name "Net-(LED17-DO)") (class "Default")
      (node (ref "LED17") (pin "DOUT") (pinfunction "DO_DOUT") (pintype "output"))
      (node (ref "LED18") (pin "DIN") (pinfunction "DI_DIN") (pintype "input"))
    )
    (net (code "23") (name "Net-(LED18-DO)") (class "Default")
      (node (ref "LED18") (pin "DOUT") (pinfunction "DO_DOUT") (pintype "output"))
      (node (ref "LED19") (pin "DIN") (pinfunction "DI_DIN") (pintype "input"))
    )
    (net (code "24") (name "Net-(LED19-DO)") (class "Default")
      (node (ref "LED19") (pin "DOUT") (pinfunction "DO_DOUT") (pintype "output"))
      (node (ref "LED20") (pin "DIN") (pinfunction "DI_DIN") (pintype "input"))
    )
    (net (code "25") (name "Net-(LED20-DO)") (class "Default")
      (node (ref "LED20") (pin "DOUT") (pinfunction "DO_DOUT") (pintype "output"))
      (node (ref "LED21") (pin "DIN") (pinfunction "DI_DIN") (pintype "input"))
    )
    (net (code "26") (name "Net-(LED21-DO)") (class "Default")
      (node (ref "LED21") (pin "DOUT") (pinfunction "DO_DOUT") (pintype "output"))
      (node (ref "LED22") (pin "DIN") (pinfunction "DI_DIN") (pintype "input"))
    )
    (net (code "27") (name "Net-(LED22-DO)") (class "Default")
      (node (ref "LED22") (pin "DOUT") (pinfunction "DO_DOUT") (pintype "output"))
      (node (ref "LED23") (pin "DIN") (pinfunction "DI_DIN") (pintype "input"))
    )
    (net (code "28") (name "Net-(LED23-DO)") (class "Default")
      (node (ref "LED23") (pin "DOUT") (pinfunction "DO_DOUT") (pintype "output"))
      (node (ref "LED24") (pin "DIN") (pinfunction "DI_DIN") (pintype "input"))
    )
    (net (code "29") (name "Net-(LED24-DO)") (class "Default")
      (node (ref "LED24") (pin "DOUT") (pinfunction "DO_DOUT") (pintype "output"))
      (node (ref "LED25") (pin "DIN") (pinfunction "DI_DIN") (pintype "input"))
    )
    (net (code "30") (name "Net-(LED25-DO)") (class "Default")
      (node (ref "LED25") (pin "DOUT") (pinfunction "DO_DOUT") (pintype "output"))
      (node (ref "LED26") (pin "DIN") (pinfunction "DI_DIN") (pintype "input"))
    )
    (net (code "31") (name "Net-(LED26-DO)") (class "Default")
      (node (ref "LED26") (pin "DOUT") (pinfunction "DO_DOUT") (pintype "output"))
      (node (ref "LED27") (pin "DIN") (pinfunction "DI_DIN") (pintype "input"))
    )
    (net (code "32") (name "Net-(LED27-DO)") (class "Default")
      (node (ref "LED27") (pin "DOUT") (pinfunction "DO_DOUT") (pintype "output"))
      (node (ref "LED28") (pin "DIN") (pinfunction "DI_DIN") (pintype "input"))
    )
    (net (code "33") (name "Net-(LED28-DO)") (class "Default")
      (node (ref "LED28") (pin "DOUT") (pinfunction "DO_DOUT") (pintype "output"))
      (node (ref "LED29") (pin "DIN") (pinfunction "DI_DIN") (pintype "input"))
    )
    (net (code "34") (name "Net-(LED29-DO)") (class "Default")
      (node (ref "LED29") (pin "DOUT") (pinfunction "DO_DOUT") (pintype "output"))
      (node (ref "LED30") (pin "DIN") (pinfunction "DI_DIN") (pintype "input"))
    )
    (net (code "35") (name "Net-(LED30-DO)") (class "Default")
      (node (ref "LED30") (pin "DOUT") (pinfunction "DO_DOUT") (pintype "output"))
      (node (ref "LED31") (pin "DIN") (pinfunction "DI_DIN") (pintype "input"))
    )
    (net (code "36") (name "Net-(LED31-DO)") (class "Default")
      (node (ref "LED31") (pin "DOUT") (pinfunction "DO_DOUT") (pintype "output"))
      (node (ref "LED32") (pin "DIN") (pinfunction "DI_DIN") (pintype "input"))
    )
    (net (code "37") (name "Net-(LED32-DO)") (class "Default")
      (node (ref "LED32") (pin "DOUT") (pinfunction "DO_DOUT") (pintype "output"))
      (node (ref "LED33") (pin "DIN") (pinfunction "DI_DIN") (pintype "input"))
    )
    (net (code "38") (name "Net-(LED33-DO)") (class "Default")
      (node (ref "LED33") (pin "DOUT") (pinfunction "DO_DOUT") (pintype "output"))
      (node (ref "LED34") (pin "DIN") (pinfunction "DI_DIN") (pintype "input"))
    )
    (net (code "39") (name "Net-(LED34-DO)") (class "Default")
      (node (ref "LED34") (pin "DOUT") (pinfunction "DO_DOUT") (pintype "output"))
      (node (ref "LED35") (pin "DIN") (pinfunction "DI_DIN") (pintype "input"))
    )
    (net (code "40") (name "Net-(LED35-DO)") (class "Default")
      (node (ref "LED35") (pin "DOUT") (pinfunction "DO_DOUT") (pintype "output"))
      (node (ref "LED36") (pin "DIN") (pinfunction "DI_DIN") (pintype "input"))
    )
    (net (code "41") (name "Net-(LED36-DO)") (class "Default")
      (node (ref "LED36") (pin "DOUT") (pinfunction "DO_DOUT") (pintype "output"))
      (node (ref "LED37") (pin "DIN") (pinfunction "DI_DIN") (pintype "input"))
    )
    (net (code "42") (name "Net-(LED37-DO)") (class "Default")
      (node (ref "LED37") (pin "DOUT") (pinfunction "DO_DOUT") (pintype "output"))
      (node (ref "LED38") (pin "DIN") (pinfunction "DI_DIN") (pintype "input"))
    )
    (net (code "43") (name "Net-(LED38-DO)") (class "Default")
      (node (ref "LED38") (pin "DOUT") (pinfunction "DO_DOUT") (pintype "output"))
      (node (ref "LED39") (pin "DIN") (pinfunction "DI_DIN") (pintype "input"))
    )
    (net (code "44") (name "Net-(LED39-DO)") (class "Default")
      (node (ref "LED39") (pin "DOUT") (pinfunction "DO_DOUT") (pintype "output"))
      (node (ref "LED40") (pin "DIN") (pinfunction "DI_DIN") (pintype "input"))
    )
    (net (code "45") (name "Net-(LED40-DO)") (class "Default")
      (node (ref "LED40") (pin "DOUT") (pinfunction "DO_DOUT") (pintype "output"))
      (node (ref "LED41") (pin "DIN") (pinfunction "DI_DIN") (pintype "input"))
    )
    (net (code "46") (name "Net-(LED41-DO)") (class "Default")
      (node (ref "LED41") (pin "DOUT") (pinfunction "DO_DOUT") (pintype "output"))
      (node (ref "LED42") (pin "DIN") (pinfunction "DI_DIN") (pintype "input"))
    )
    (net (code "47") (name "Net-(LED42-DO)") (class "Default")
      (node (ref "LED42") (pin "DOUT") (pinfunction "DO_DOUT") (pintype "output"))
      (node (ref "LED43") (pin "DIN") (pinfunction "DI_DIN") (pintype "input"))
    )
    (net (code "48") (name "Net-(LED43-DO)") (class "Default")
      (node (ref "LED43") (pin "DOUT") (pinfunction "DO_DOUT") (pintype "output"))
      (node (ref "LED44") (pin "DIN") (pinfunction "DI_DIN") (pintype "input"))
    )
    (net (code "49") (name "Net-(LED44-DO)") (class "Default")
      (node (ref "LED44") (pin "DOUT") (pinfunction "DO_DOUT") (pintype "output"))
      (node (ref "LED45") (pin "DIN") (pinfunction "DI_DIN") (pintype "input"))
    )
    (net (code "50") (name "Net-(LED45-DO)") (class "Default")
      (node (ref "LED45") (pin "DOUT") (pinfunction "DO_DOUT") (pintype "output"))
      (node (ref "LED46") (pin "DIN") (pinfunction "DI_DIN") (pintype "input"))
    )
    (net (code "51") (name "Net-(LED46-DO)") (class "Default")
      (node (ref "LED46") (pin "DOUT") (pinfunction "DO_DOUT") (pintype "output"))
      (node (ref "LED47") (pin "DIN") (pinfunction "DI_DIN") (pintype "input"))
    )
    (net (code "52") (name "Net-(LED47-DO)") (class "Default")
      (node (ref "LED47") (pin "DOUT") (pinfunction "DO_DOUT") (pintype "output"))
      (node (ref "LED48") (pin "DIN") (pinfunction "DI_DIN") (pintype "input"))
    )
    (net (code "53") (name "Net-(LED48-DO)") (class "Default")
      (node (ref "LED48") (pin "DOUT") (pinfunction "DO_DOUT") (pintype "output"))
      (node (ref "LED49") (pin "DIN") (pinfunction "DI_DIN") (pintype "input"))
    )
    (net (code "54") (name "Net-(LED49-DO)") (class "Default")
      (node (ref "LED49") (pin "DOUT") (pinfunction "DO_DOUT") (pintype "output"))
      (node (ref "LED50") (pin "DIN") (pinfunction "DI_DIN") (pintype "input"))
    )
    (net (code "55") (name "Net-(LED50-DO)") (class "Default")
      (node (ref "LED50") (pin "DOUT") (pinfunction "DO_DOUT") (pintype "output"))
      (node (ref "LED51") (pin "DIN") (pinfunction "DI_DIN") (pintype "input"))
    )
    (net (code "56") (name "Net-(LED51-DO)") (class "Default")
      (node (ref "LED51") (pin "DOUT") (pinfunction "DO_DOUT") (pintype "output"))
      (node (ref "LED52") (pin "DIN") (pinfunction "DI_DIN") (pintype "input"))
    )
    (net (code "57") (name "Net-(LED52-DO)") (class "Default")
      (node (ref "LED52") (pin "DOUT") (pinfunction "DO_DOUT") (pintype "output"))
      (node (ref "LED53") (pin "DIN") (pinfunction "DI_DIN") (pintype "input"))
    )
    (net (code "58") (name "Net-(LED53-DO)") (class "Default")
      (node (ref "LED53") (pin "DOUT") (pinfunction "DO_DOUT") (pintype "output"))
      (node (ref "LED54") (pin "DIN") (pinfunction "DI_DIN") (pintype "input"))
    )
    (net (code "59") (name "Net-(LED54-DO)") (class "Default")
      (node (ref "LED54") (pin "DOUT") (pinfunction "DO_DOUT") (pintype "output"))
      (node (ref "LED55") (pin "DIN") (pinfunction "DI_DIN") (pintype "input"))
    )
    (net (code "60") (name "Net-(LED55-DO)") (class "Default")
      (node (ref "LED55") (pin "DOUT") (pinfunction "DO_DOUT") (pintype "output"))
      (node (ref "LED56") (pin "DIN") (pinfunction "DI_DIN") (pintype "input"))
    )
    (net (code "61") (name "Net-(LED56-DO)") (class "Default")
      (node (ref "LED56") (pin "DOUT") (pinfunction "DO_DOUT") (pintype "output"))
      (node (ref "LED57") (pin "DIN") (pinfunction "DI_DIN") (pintype "input"))
    )
    (net (code "62") (name "Net-(LED57-DO)") (class "Default")
      (node (ref "LED57") (pin "DOUT") (pinfunction "DO_DOUT") (pintype "output"))
      (node (ref "LED58") (pin "DIN") (pinfunction "DI_DIN") (pintype "input"))
    )
    (net (code "63") (name "Net-(LED58-DO)") (class "Default")
      (node (ref "LED58") (pin "DOUT") (pinfunction "DO_DOUT") (pintype "output"))
      (node (ref "LED59") (pin "DIN") (pinfunction "DI_DIN") (pintype "input"))
    )
    (net (code "64") (name "Net-(LED59-DO)") (class "Default")
      (node (ref "LED59") (pin "DOUT") (pinfunction "DO_DOUT") (pintype "output"))
      (node (ref "LED60") (pin "DIN") (pinfunction "DI_DIN") (pintype "input"))
    )
    (net (code "65") (name "Net-(LED60-DO)") (class "Default")
      (node (ref "LED60") (pin "DOUT") (pinfunction "DO_DOUT") (pintype "output"))
      (node (ref "LED61") (pin "DIN") (pinfunction "DI_DIN") (pintype "input"))
    )
    (net (code "66") (name "Net-(LED61-DO)") (class "Default")
      (node (ref "LED61") (pin "DOUT") (pinfunction "DO_DOUT") (pintype "output"))
      (node (ref "LED62") (pin "DIN") (pinfunction "DI_DIN") (pintype "input"))
    )
    (net (code "67") (name "Net-(LED62-DO)") (class "Default")
      (node (ref "LED62") (pin "DOUT") (pinfunction "DO_DOUT") (pintype "output"))
      (node (ref "LED63") (pin "DIN") (pinfunction "DI_DIN") (pintype "input"))
    )
    (net (code "68") (name "Net-(LED63-DO)") (class "Default")
      (node (ref "LED63") (pin "DOUT") (pinfunction "DO_DOUT") (pintype "output"))
      (node (ref "LED64") (pin "DIN") (pinfunction "DI_DIN") (pintype "input"))
    )
    (net (code "69") (name "Net-(LED64-DO)") (class "Default")
      (node (ref "LED64") (pin "DOUT") (pinfunction "DO_DOUT") (pintype "output"))
      (node (ref "LED65") (pin "DIN") (pinfunction "DI_DIN") (pintype "input"))
    )
    (net (code "70") (name "Net-(LED65-DO)") (class "Default")
      (node (ref "LED65") (pin "DOUT") (pinfunction "DO_DOUT") (pintype "output"))
      (node (ref "LED66") (pin "DIN") (pinfunction "DI_DIN") (pintype "input"))
    )
    (net (code "71") (name "Net-(LED66-DO)") (class "Default")
      (node (ref "LED66") (pin "DOUT") (pinfunction "DO_DOUT") (pintype "output"))
      (node (ref "LED67") (pin "DIN") (pinfunction "DI_DIN") (pintype "input"))
    )
    (net (code "72") (name "Net-(LED67-DO)") (class "Default")
      (node (ref "LED67") (pin "DOUT") (pinfunction "DO_DOUT") (pintype "output"))
      (node (ref "LED68") (pin "DIN") (pinfunction "DI_DIN") (pintype "input"))
    )
    (net (code "73") (name "Net-(LED68-DO)") (class "Default")
      (node (ref "LED68") (pin "DOUT") (pinfunction "DO_DOUT") (pintype "output"))
      (node (ref "LED69") (pin "DIN") (pinfunction "DI_DIN") (pintype "input"))
    )
    (net (code "74") (name "Net-(LED69-DO)") (class "Default")
      (node (ref "LED69") (pin "DOUT") (pinfunction "DO_DOUT") (pintype "output"))
      (node (ref "LED70") (pin "DIN") (pinfunction "DI_DIN") (pintype "input"))
    )
    (net (code "75") (name "Net-(LED70-DO)") (class "Default")
      (node (ref "LED70") (pin "DOUT") (pinfunction "DO_DOUT") (pintype "output"))
      (node (ref "LED71") (pin "DIN") (pinfunction "DI_DIN") (pintype "input"))
    )
    (net (code "76") (name "Net-(LED71-DO)") (class "Default")
      (node (ref "LED71") (pin "DOUT") (pinfunction "DO_DOUT") (pintype "output"))
      (node (ref "LED72") (pin "DIN") (pinfunction "DI_DIN") (pintype "input"))
    )
    (net (code "77") (name "Net-(LED72-DO)") (class "Default")
      (node (ref "LED72") (pin "DOUT") (pinfunction "DO_DOUT") (pintype "output"))
      (node (ref "LED73") (pin "DIN") (pinfunction "DI_DIN") (pintype "input"))
    )
    (net (code "78") (name "Net-(LED73-DO)") (class "Default")
      (node (ref "LED73") (pin "DOUT") (pinfunction "DO_DOUT") (pintype "output"))
      (node (ref "LED74") (pin "DIN") (pinfunction "DI_DIN") (pintype "input"))
    )
    (net (code "79") (name "Net-(LED74-DO)") (class "Default")
      (node (ref "LED74") (pin "DOUT") (pinfunction "DO_DOUT") (pintype "output"))
      (node (ref "LED75") (pin "DIN") (pinfunction "DI_DIN") (pintype "input"))
    )
    (net (code "80") (name "Net-(LED75-DO)") (class "Default")
      (node (ref "LED75") (pin "DOUT") (pinfunction "DO_DOUT") (pintype "output"))
      (node (ref "LED76") (pin "DIN") (pinfunction "DI_DIN") (pintype "input"))
    )
    (net (code "81") (name "Net-(LED76-DO)") (class "Default")
      (node (ref "LED76") (pin "DOUT") (pinfunction "DO_DOUT") (pintype "output"))
      (node (ref "LED77") (pin "DIN") (pinfunction "DI_DIN") (pintype "input"))
    )
    (net (code "82") (name "Net-(LED77-DO)") (class "Default")
      (node (ref "LED77") (pin "DOUT") (pinfunction "DO_DOUT") (pintype "output"))
      (node (ref "LED78") (pin "DIN") (pinfunction "DI_DIN") (pintype "input"))
    )
    (net (code "83") (name "Net-(LED78-DO)") (class "Default")
      (node (ref "LED78") (pin "DOUT") (pinfunction "DO_DOUT") (pintype "output"))
      (node (ref "LED79") (pin "DIN") (pinfunction "DI_DIN") (pintype "input"))
    )
    (net (code "84") (name "Net-(LED79-DO)") (class "Default")
      (node (ref "LED79") (pin "DOUT") (pinfunction "DO_DOUT") (pintype "output"))
      (node (ref "LED80") (pin "DIN") (pinfunction "DI_DIN") (pintype "input"))
    )
    (net (code "85") (name "Net-(LED80-DO)") (class "Default")
      (node (ref "LED80") (pin "DOUT") (pinfunction "DO_DOUT") (pintype "output"))
      (node (ref "LED81") (pin "DIN") (pinfunction "DI_DIN") (pintype "input"))
    )
    (net (code "86") (name "Net-(LED81-DO)") (class "Default")
      (node (ref "LED81") (pin "DOUT") (pinfunction "DO_DOUT") (pintype "output"))
      (node (ref "LED82") (pin "DIN") (pinfunction "DI_DIN") (pintype "input"))
    )
    (net (code "87") (name "Net-(LED82-DO)") (class "Default")
      (node (ref "LED82") (pin "DOUT") (pinfunction "DO_DOUT") (pintype "output"))
      (node (ref "LED83") (pin "DIN") (pinfunction "DI_DIN") (pintype "input"))
    )
    (net (code "88") (name "Net-(LED83-DO)") (class "Default")
      (node (ref "LED83") (pin "DOUT") (pinfunction "DO_DOUT") (pintype "output"))
      (node (ref "LED84") (pin "DIN") (pinfunction "DI_DIN") (pintype "input"))
    )
    (net (code "89") (name "Net-(LED84-DO)") (class "Default")
      (node (ref "LED84") (pin "DOUT") (pinfunction "DO_DOUT") (pintype "output"))
      (node (ref "LED85") (pin "DIN") (pinfunction "DI_DIN") (pintype "input"))
    )
    (net (code "90") (name "Net-(LED85-DO)") (class "Default")
      (node (ref "LED85") (pin "DOUT") (pinfunction "DO_DOUT") (pintype "output"))
      (node (ref "LED86") (pin "DIN") (pinfunction "DI_DIN") (pintype "input"))
    )
    (net (code "91") (name "Net-(LED86-DO)") (class "Default")
      (node (ref "LED86") (pin "DOUT") (pinfunction "DO_DOUT") (pintype "output"))
      (node (ref "LED87") (pin "DIN") (pinfunction "DI_DIN") (pintype "input"))
    )
    (net (code "92") (name "Net-(LED87-DO)") (class "Default")
      (node (ref "LED87") (pin "DOUT") (pinfunction "DO_DOUT") (pintype "output"))
      (node (ref "LED88") (pin "DIN") (pinfunction "DI_DIN") (pintype "input"))
    )
    (net (code "93") (name "Net-(LED88-DO)") (class "Default")
      (node (ref "LED88") (pin "DOUT") (pinfunction "DO_DOUT") (pintype "output"))
      (node (ref "LED89") (pin "DIN") (pinfunction "DI_DIN") (pintype "input"))
    )
    (net (code "94") (name "Net-(LED89-DO)") (class "Default")
      (node (ref "LED89") (pin "DOUT") (pinfunction "DO_DOUT") (pintype "output"))
      (node (ref "LED90") (pin "DIN") (pinfunction "DI_DIN") (pintype "input"))
    )
    (net (code "95") (name "Net-(LED90-DO)") (class "Default")
      (node (ref "LED90") (pin "DOUT") (pinfunction "DO_DOUT") (pintype "output"))
      (node (ref "LED91") (pin "DIN") (pinfunction "DI_DIN") (pintype "input"))
    )
    (net (code "96") (name "Net-(LED91-DO)") (class "Default")
      (node (ref "LED91") (pin "DOUT") (pinfunction "DO_DOUT") (pintype "output"))
      (node (ref "LED92") (pin "DIN") (pinfunction "DI_DIN") (pintype "input"))
    )
    (net (code "97") (name "Net-(LED92-DO)") (class "Default")
      (node (ref "LED92") (pin "DOUT") (pinfunction "DO_DOUT") (pintype "output"))
      (node (ref "LED93") (pin "DIN") (pinfunction "DI_DIN") (pintype "input"))
    )
    (net (code "98") (name "Net-(LED93-DO)") (class "Default")
      (node (ref "LED93") (pin "DOUT") (pinfunction "DO_DOUT") (pintype "output"))
      (node (ref "LED94") (pin "DIN") (pinfunction "DI_DIN") (pintype "input"))
    )
    (net (code "99") (name "Net-(LED94-DO)") (class "Default")
      (node (ref "LED94") (pin "DOUT") (pinfunction "DO_DOUT") (pintype "output"))
      (node (ref "LED95") (pin "DIN") (pinfunction "DI_DIN") (pintype "input"))
    )
  )
)
